# hub_keyboard.net
KiCad netlist of a schematic drawn in EAGLE
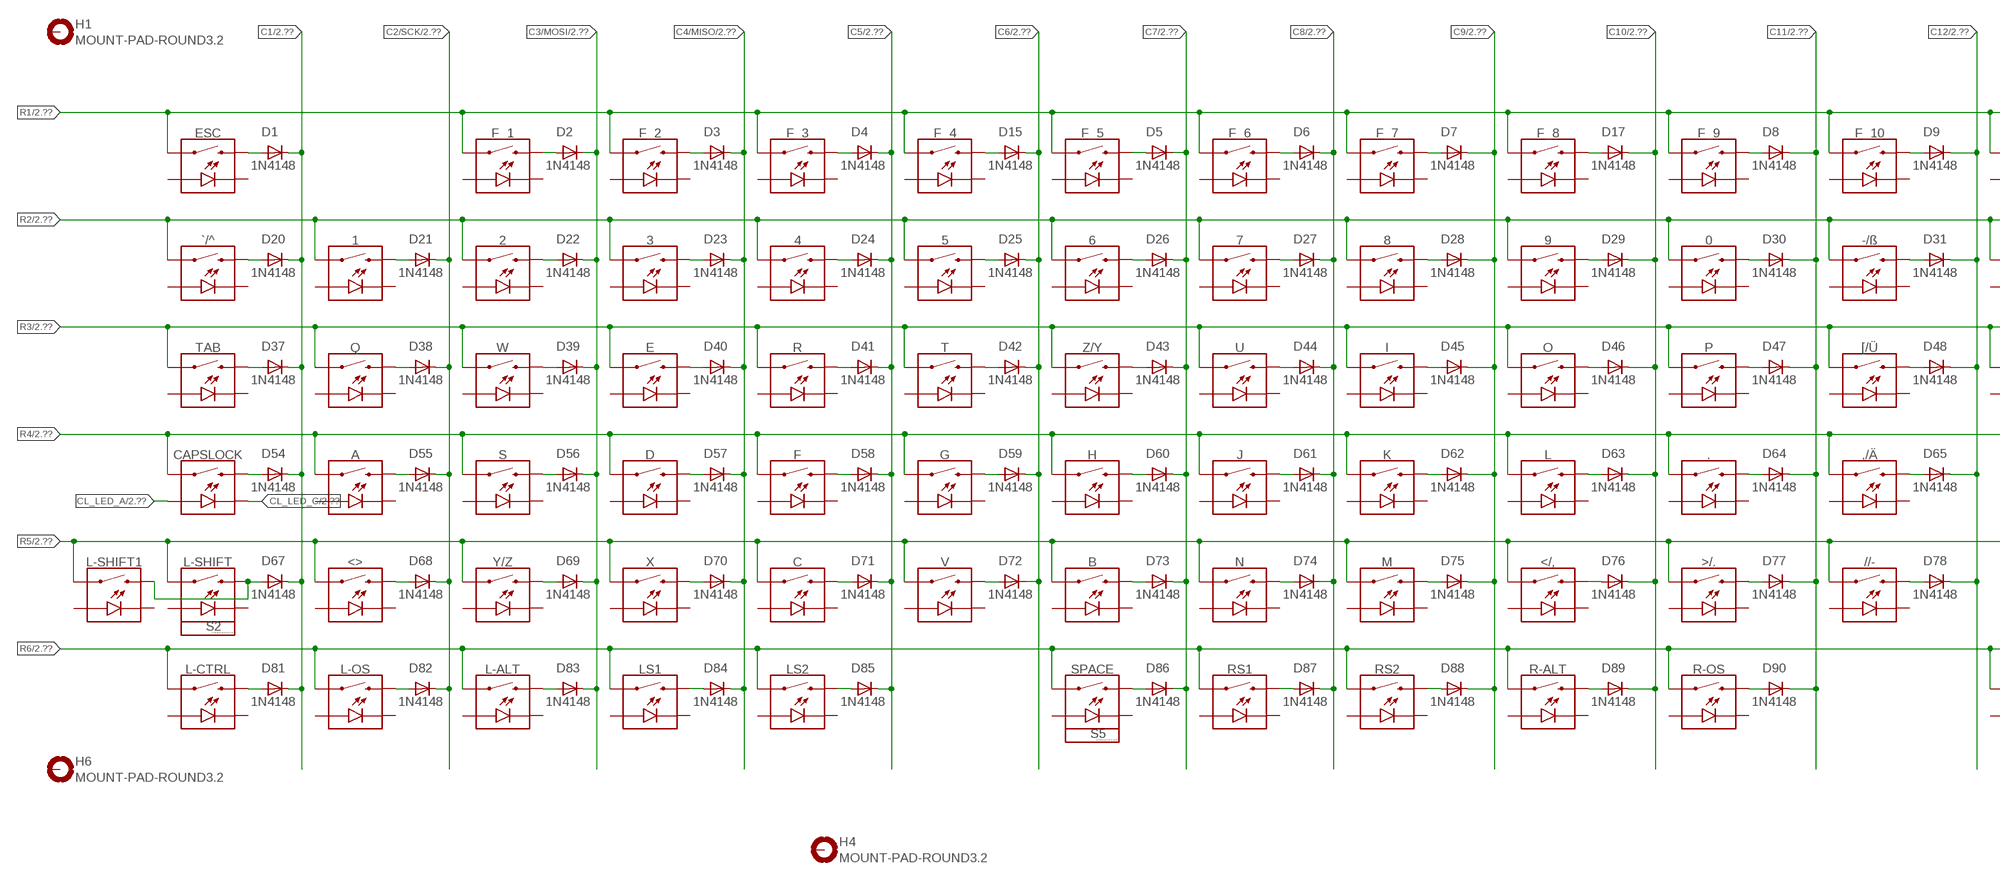
[diagram p0: schematic, sheet 1, part 1 of 2]
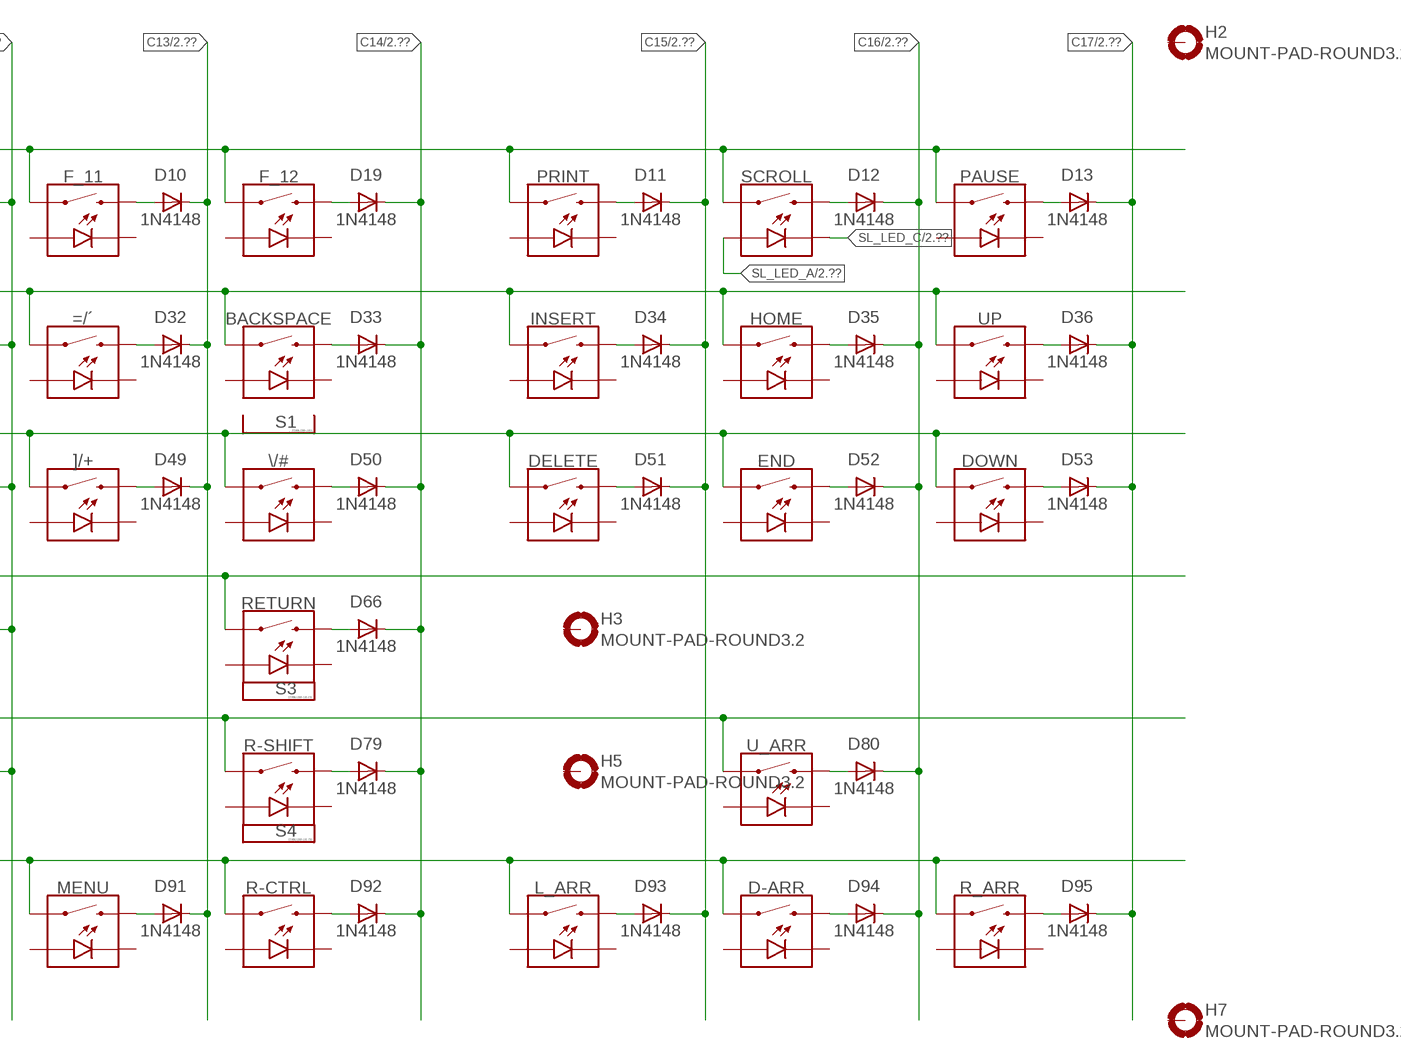
[diagram p1: schematic, sheet 1, part 2 of 2]
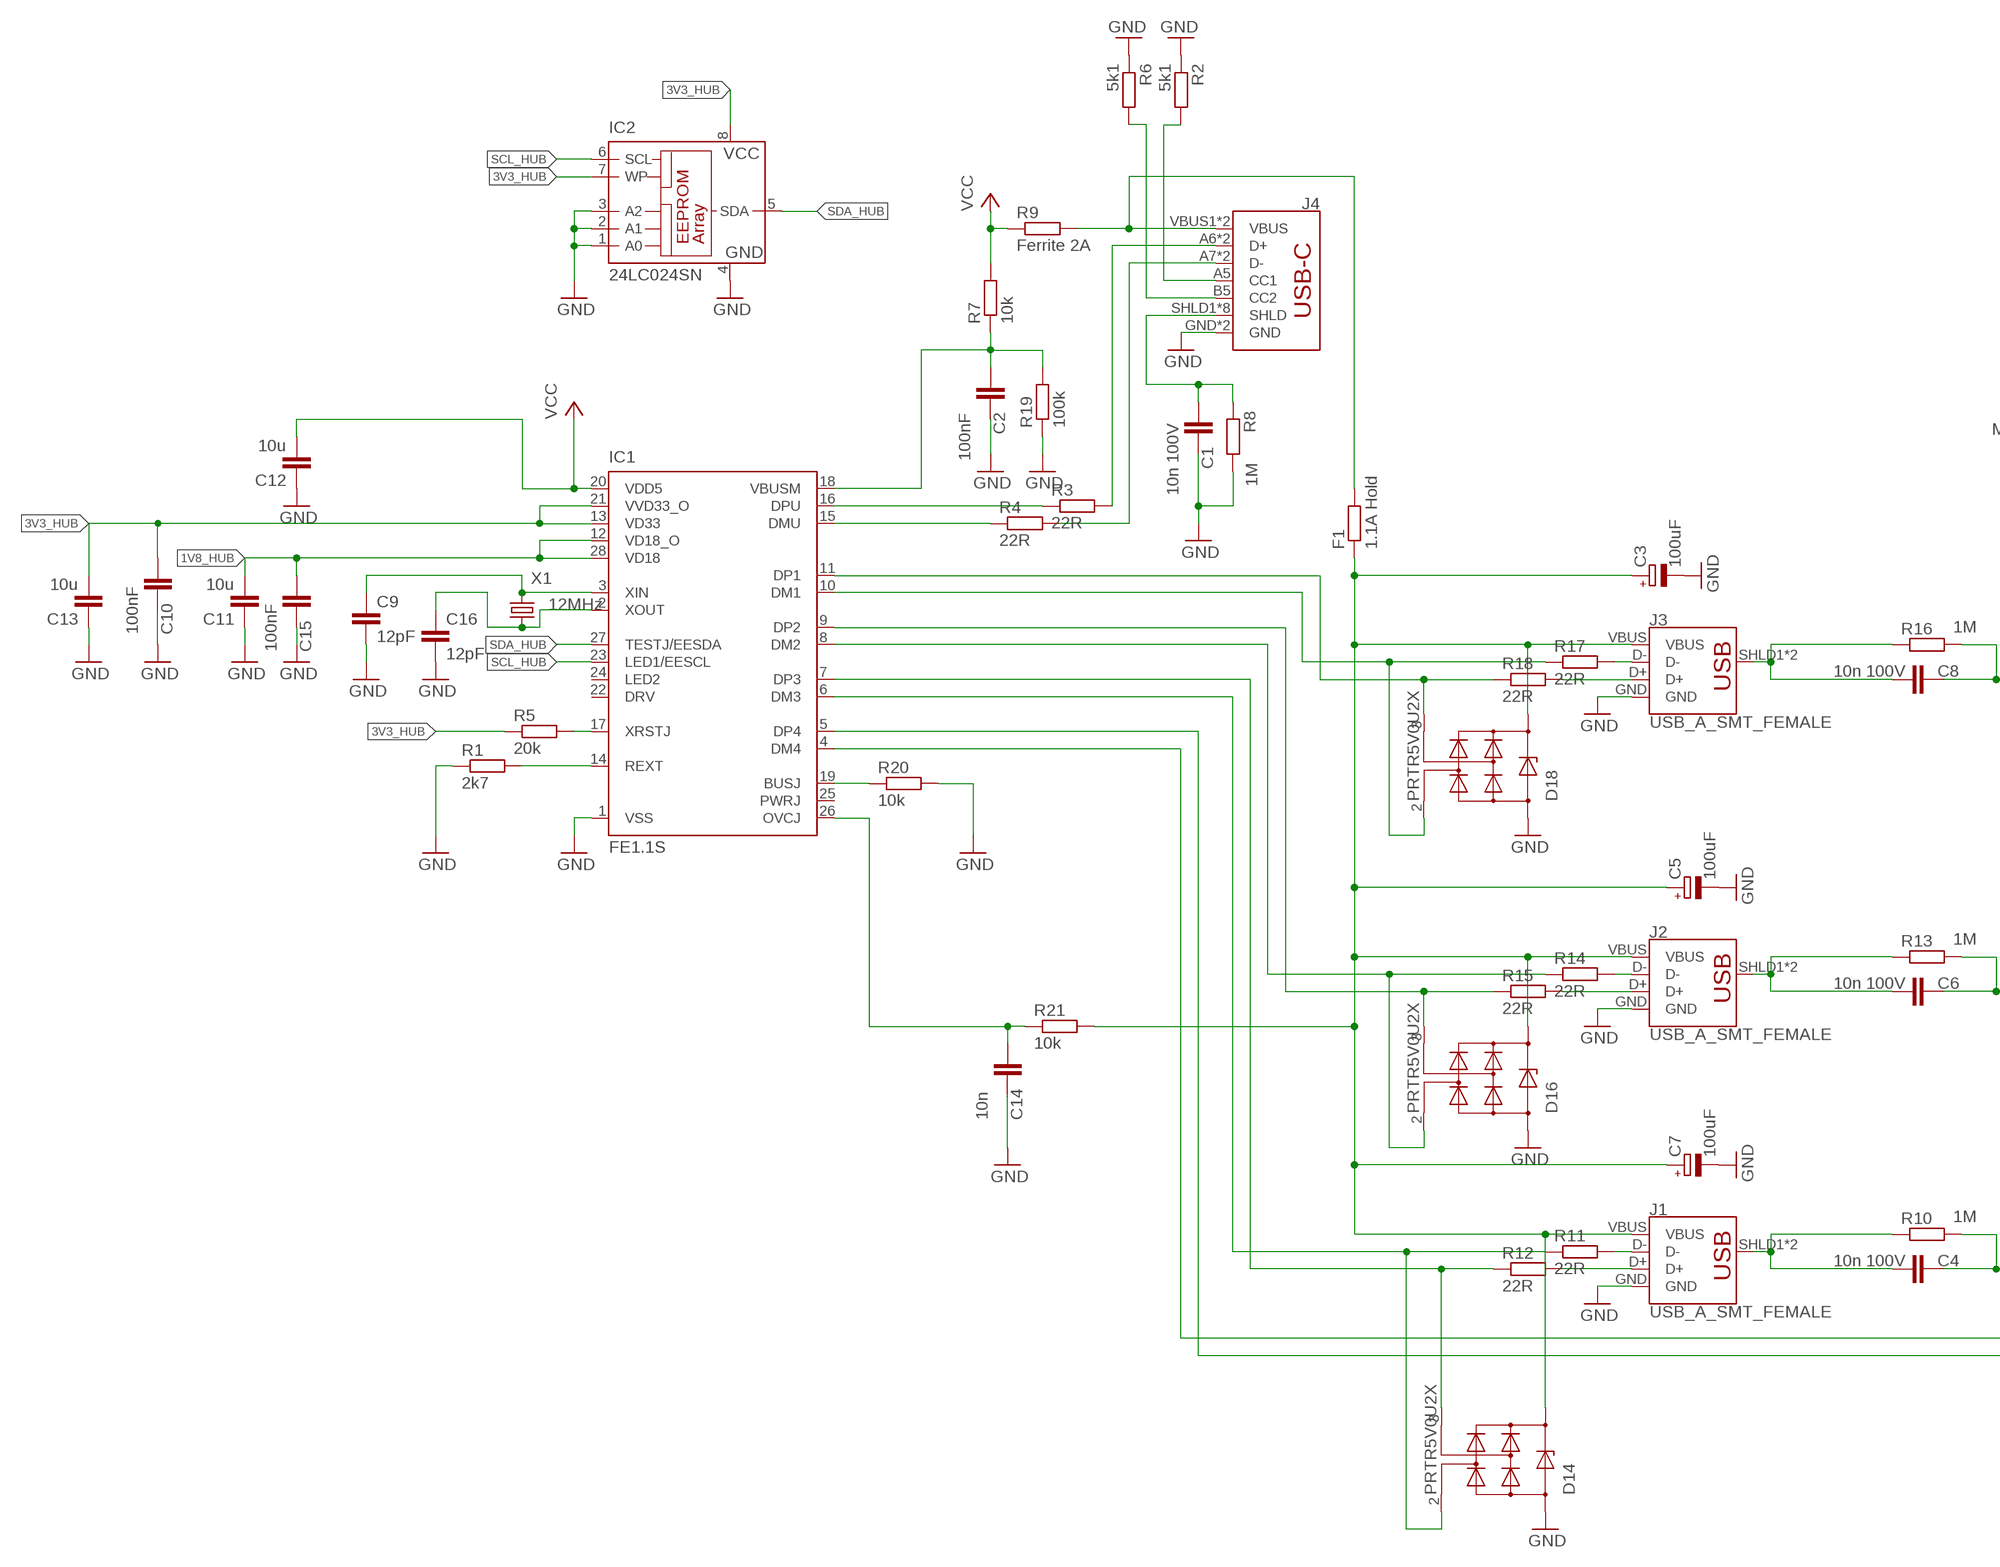
[diagram p2: schematic, sheet 2, part 1 of 2]
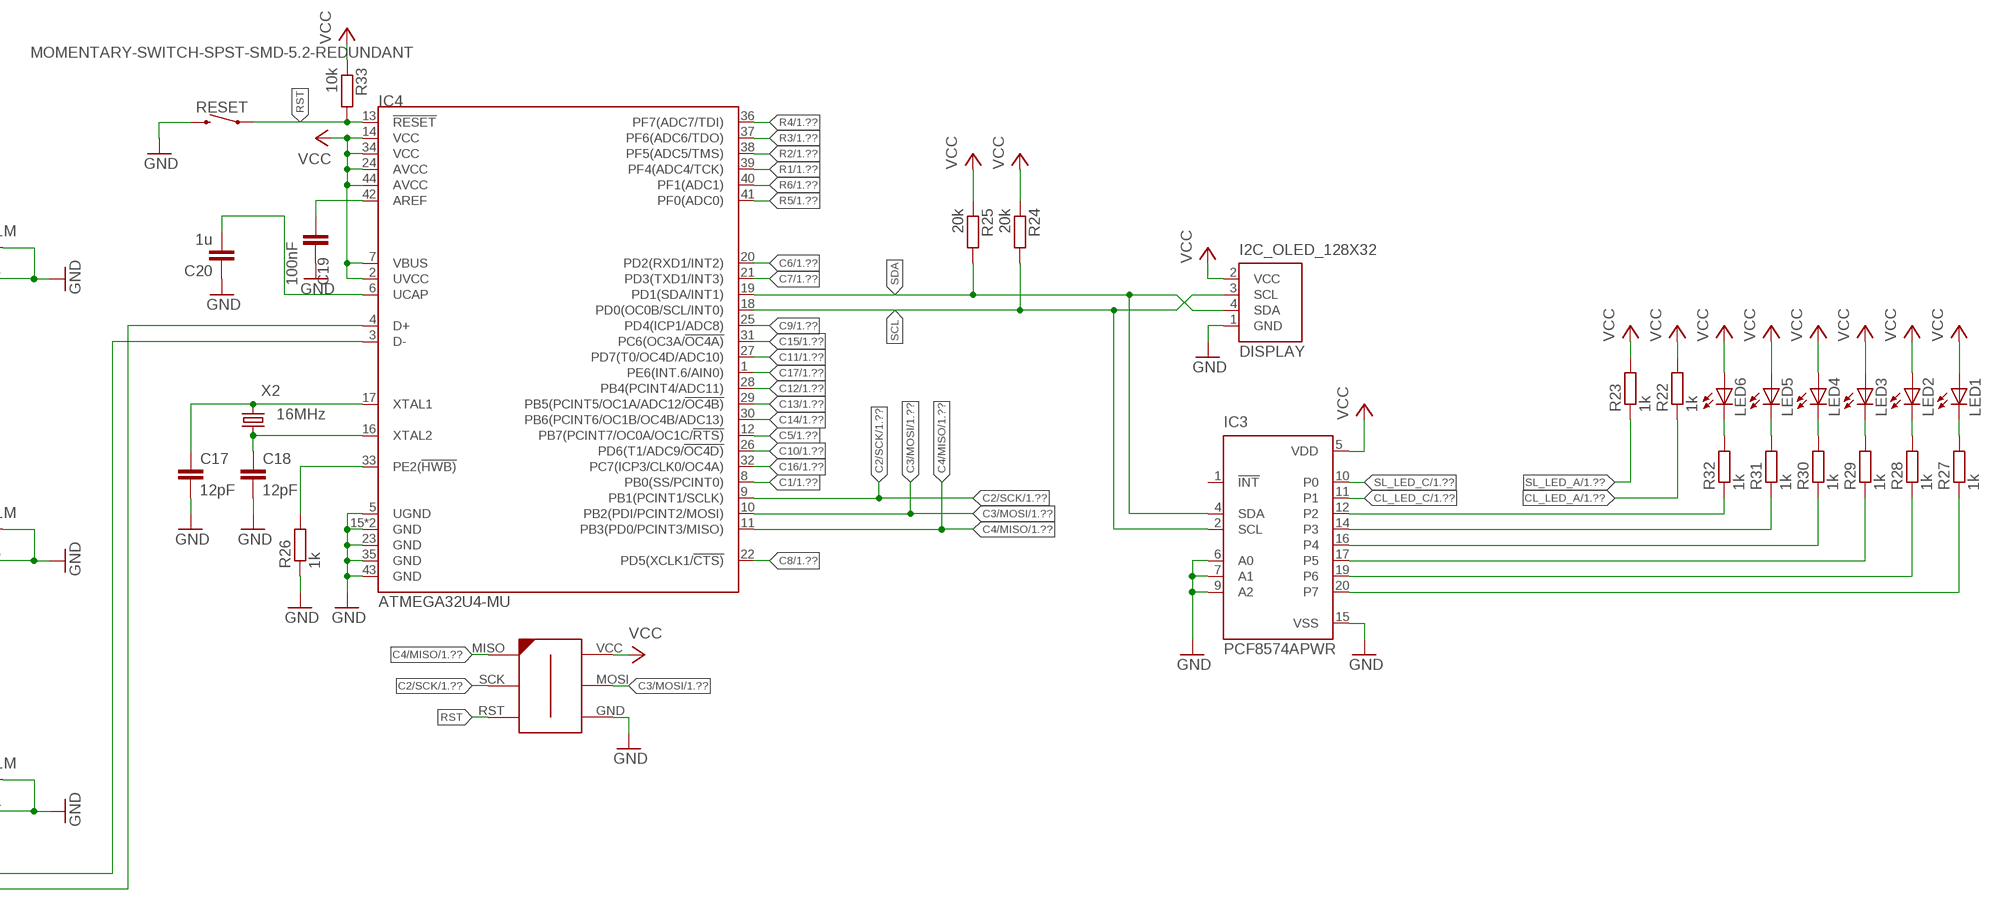
[diagram p3: schematic, sheet 2, part 2 of 2]

(export (version "E")
  (design (tool "Eeschema 10.0.6"))
  (components
    (comp (ref ",/Ä")
      (value "MECHANICAL-KEYBOARD1U")
      (footprint "eagle-import:CHERRY-MX-LED-1U")
      (libsource (lib "eagle-import") (part "MECHANICAL-KEYBOARD1U"))
    )
    (comp (ref "-/ß")
      (value "MECHANICAL-KEYBOARD1U")
      (footprint "eagle-import:CHERRY-MX-LED-1U")
      (libsource (lib "eagle-import") (part "MECHANICAL-KEYBOARD1U"))
    )
    (comp (ref ".")
      (value "MECHANICAL-KEYBOARD1U")
      (footprint "eagle-import:CHERRY-MX-LED-1U")
      (libsource (lib "eagle-import") (part "MECHANICAL-KEYBOARD1U"))
    )
    (comp (ref "//-")
      (value "MECHANICAL-KEYBOARD1U")
      (footprint "eagle-import:CHERRY-MX-LED-1U")
      (libsource (lib "eagle-import") (part "MECHANICAL-KEYBOARD1U"))
    )
    (comp (ref "0")
      (value "MECHANICAL-KEYBOARD1U")
      (footprint "eagle-import:CHERRY-MX-LED-1U")
      (libsource (lib "eagle-import") (part "MECHANICAL-KEYBOARD1U"))
    )
    (comp (ref "1")
      (value "MECHANICAL-KEYBOARD1U")
      (footprint "eagle-import:CHERRY-MX-LED-1U")
      (libsource (lib "eagle-import") (part "MECHANICAL-KEYBOARD1U"))
    )
    (comp (ref "2")
      (value "MECHANICAL-KEYBOARD1U")
      (footprint "eagle-import:CHERRY-MX-LED-1U")
      (libsource (lib "eagle-import") (part "MECHANICAL-KEYBOARD1U"))
    )
    (comp (ref "3")
      (value "MECHANICAL-KEYBOARD1U")
      (footprint "eagle-import:CHERRY-MX-LED-1U")
      (libsource (lib "eagle-import") (part "MECHANICAL-KEYBOARD1U"))
    )
    (comp (ref "4")
      (value "MECHANICAL-KEYBOARD1U")
      (footprint "eagle-import:CHERRY-MX-LED-1U")
      (libsource (lib "eagle-import") (part "MECHANICAL-KEYBOARD1U"))
    )
    (comp (ref "5")
      (value "MECHANICAL-KEYBOARD1U")
      (footprint "eagle-import:CHERRY-MX-LED-1U")
      (libsource (lib "eagle-import") (part "MECHANICAL-KEYBOARD1U"))
    )
    (comp (ref "6")
      (value "MECHANICAL-KEYBOARD1U")
      (footprint "eagle-import:CHERRY-MX-LED-1U")
      (libsource (lib "eagle-import") (part "MECHANICAL-KEYBOARD1U"))
    )
    (comp (ref "7")
      (value "MECHANICAL-KEYBOARD1U")
      (footprint "eagle-import:CHERRY-MX-LED-1U")
      (libsource (lib "eagle-import") (part "MECHANICAL-KEYBOARD1U"))
    )
    (comp (ref "8")
      (value "MECHANICAL-KEYBOARD1U")
      (footprint "eagle-import:CHERRY-MX-LED-1U")
      (libsource (lib "eagle-import") (part "MECHANICAL-KEYBOARD1U"))
    )
    (comp (ref "9")
      (value "MECHANICAL-KEYBOARD1U")
      (footprint "eagle-import:CHERRY-MX-LED-1U")
      (libsource (lib "eagle-import") (part "MECHANICAL-KEYBOARD1U"))
    )
    (comp (ref "</,")
      (value "MECHANICAL-KEYBOARD1U")
      (footprint "eagle-import:CHERRY-MX-LED-1U")
      (libsource (lib "eagle-import") (part "MECHANICAL-KEYBOARD1U"))
    )
    (comp (ref "<>")
      (value "MECHANICAL-KEYBOARD1U")
      (footprint "eagle-import:CHERRY-MX-LED-1U")
      (libsource (lib "eagle-import") (part "MECHANICAL-KEYBOARD1U"))
    )
    (comp (ref "=/´")
      (value "MECHANICAL-KEYBOARD1U")
      (footprint "eagle-import:CHERRY-MX-LED-1U")
      (libsource (lib "eagle-import") (part "MECHANICAL-KEYBOARD1U"))
    )
    (comp (ref ">/.")
      (value "MECHANICAL-KEYBOARD1U")
      (footprint "eagle-import:CHERRY-MX-LED-1U")
      (libsource (lib "eagle-import") (part "MECHANICAL-KEYBOARD1U"))
    )
    (comp (ref "A")
      (value "MECHANICAL-KEYBOARD1U")
      (footprint "eagle-import:CHERRY-MX-LED-1U")
      (libsource (lib "eagle-import") (part "MECHANICAL-KEYBOARD1U"))
    )
    (comp (ref "B")
      (value "MECHANICAL-KEYBOARD1U")
      (footprint "eagle-import:CHERRY-MX-LED-1U")
      (libsource (lib "eagle-import") (part "MECHANICAL-KEYBOARD1U"))
    )
    (comp (ref "BACKSPACE")
      (value "MECHANICAL-KEYBOARD2U")
      (footprint "eagle-import:CHERRY-MX-LED-1X2U")
      (libsource (lib "eagle-import") (part "MECHANICAL-KEYBOARD2U"))
    )
    (comp (ref "C")
      (value "MECHANICAL-KEYBOARD1U")
      (footprint "eagle-import:CHERRY-MX-LED-1U")
      (libsource (lib "eagle-import") (part "MECHANICAL-KEYBOARD1U"))
    )
    (comp (ref "CAPSLOCK")
      (value "MECHANICAL-KEYBOARD1.75U")
      (footprint "eagle-import:CHERRY-MX-LED-1.75U")
      (libsource (lib "eagle-import") (part "MECHANICAL-KEYBOARD1.75U"))
    )
    (comp (ref "D")
      (value "MECHANICAL-KEYBOARD1U")
      (footprint "eagle-import:CHERRY-MX-LED-1U")
      (libsource (lib "eagle-import") (part "MECHANICAL-KEYBOARD1U"))
    )
    (comp (ref "D-ARR")
      (value "MECHANICAL-KEYBOARD1U")
      (footprint "eagle-import:CHERRY-MX-LED-1U")
      (libsource (lib "eagle-import") (part "MECHANICAL-KEYBOARD1U"))
    )
    (comp (ref "D1")
      (value "1N4148")
      (footprint "eagle-import:SOD123")
      (libsource (lib "eagle-import") (part "DIODE-SOD123"))
    )
    (comp (ref "D2")
      (value "1N4148")
      (footprint "eagle-import:SOD123")
      (libsource (lib "eagle-import") (part "DIODE-SOD123"))
    )
    (comp (ref "D3")
      (value "1N4148")
      (footprint "eagle-import:SOD123")
      (libsource (lib "eagle-import") (part "DIODE-SOD123"))
    )
    (comp (ref "D4")
      (value "1N4148")
      (footprint "eagle-import:SOD123")
      (libsource (lib "eagle-import") (part "DIODE-SOD123"))
    )
    (comp (ref "D5")
      (value "1N4148")
      (footprint "eagle-import:SOD123")
      (libsource (lib "eagle-import") (part "DIODE-SOD123"))
    )
    (comp (ref "D6")
      (value "1N4148")
      (footprint "eagle-import:SOD123")
      (libsource (lib "eagle-import") (part "DIODE-SOD123"))
    )
    (comp (ref "D7")
      (value "1N4148")
      (footprint "eagle-import:SOD123")
      (libsource (lib "eagle-import") (part "DIODE-SOD123"))
    )
    (comp (ref "D8")
      (value "1N4148")
      (footprint "eagle-import:SOD123")
      (libsource (lib "eagle-import") (part "DIODE-SOD123"))
    )
    (comp (ref "D9")
      (value "1N4148")
      (footprint "eagle-import:SOD123")
      (libsource (lib "eagle-import") (part "DIODE-SOD123"))
    )
    (comp (ref "D10")
      (value "1N4148")
      (footprint "eagle-import:SOD123")
      (libsource (lib "eagle-import") (part "DIODE-SOD123"))
    )
    (comp (ref "D11")
      (value "1N4148")
      (footprint "eagle-import:SOD123")
      (libsource (lib "eagle-import") (part "DIODE-SOD123"))
    )
    (comp (ref "D12")
      (value "1N4148")
      (footprint "eagle-import:SOD123")
      (libsource (lib "eagle-import") (part "DIODE-SOD123"))
    )
    (comp (ref "D13")
      (value "1N4148")
      (footprint "eagle-import:SOD123")
      (libsource (lib "eagle-import") (part "DIODE-SOD123"))
    )
    (comp (ref "D15")
      (value "1N4148")
      (footprint "eagle-import:SOD123")
      (libsource (lib "eagle-import") (part "DIODE-SOD123"))
    )
    (comp (ref "D17")
      (value "1N4148")
      (footprint "eagle-import:SOD123")
      (libsource (lib "eagle-import") (part "DIODE-SOD123"))
    )
    (comp (ref "D19")
      (value "1N4148")
      (footprint "eagle-import:SOD123")
      (libsource (lib "eagle-import") (part "DIODE-SOD123"))
    )
    (comp (ref "D20")
      (value "1N4148")
      (footprint "eagle-import:SOD123")
      (libsource (lib "eagle-import") (part "DIODE-SOD123"))
    )
    (comp (ref "D21")
      (value "1N4148")
      (footprint "eagle-import:SOD123")
      (libsource (lib "eagle-import") (part "DIODE-SOD123"))
    )
    (comp (ref "D22")
      (value "1N4148")
      (footprint "eagle-import:SOD123")
      (libsource (lib "eagle-import") (part "DIODE-SOD123"))
    )
    (comp (ref "D23")
      (value "1N4148")
      (footprint "eagle-import:SOD123")
      (libsource (lib "eagle-import") (part "DIODE-SOD123"))
    )
    (comp (ref "D24")
      (value "1N4148")
      (footprint "eagle-import:SOD123")
      (libsource (lib "eagle-import") (part "DIODE-SOD123"))
    )
    (comp (ref "D25")
      (value "1N4148")
      (footprint "eagle-import:SOD123")
      (libsource (lib "eagle-import") (part "DIODE-SOD123"))
    )
    (comp (ref "D26")
      (value "1N4148")
      (footprint "eagle-import:SOD123")
      (libsource (lib "eagle-import") (part "DIODE-SOD123"))
    )
    (comp (ref "D27")
      (value "1N4148")
      (footprint "eagle-import:SOD123")
      (libsource (lib "eagle-import") (part "DIODE-SOD123"))
    )
    (comp (ref "D28")
      (value "1N4148")
      (footprint "eagle-import:SOD123")
      (libsource (lib "eagle-import") (part "DIODE-SOD123"))
    )
    (comp (ref "D29")
      (value "1N4148")
      (footprint "eagle-import:SOD123")
      (libsource (lib "eagle-import") (part "DIODE-SOD123"))
    )
    (comp (ref "D30")
      (value "1N4148")
      (footprint "eagle-import:SOD123")
      (libsource (lib "eagle-import") (part "DIODE-SOD123"))
    )
    (comp (ref "D31")
      (value "1N4148")
      (footprint "eagle-import:SOD123")
      (libsource (lib "eagle-import") (part "DIODE-SOD123"))
    )
    (comp (ref "D32")
      (value "1N4148")
      (footprint "eagle-import:SOD123")
      (libsource (lib "eagle-import") (part "DIODE-SOD123"))
    )
    (comp (ref "D33")
      (value "1N4148")
      (footprint "eagle-import:SOD123")
      (libsource (lib "eagle-import") (part "DIODE-SOD123"))
    )
    (comp (ref "D34")
      (value "1N4148")
      (footprint "eagle-import:SOD123")
      (libsource (lib "eagle-import") (part "DIODE-SOD123"))
    )
    (comp (ref "D35")
      (value "1N4148")
      (footprint "eagle-import:SOD123")
      (libsource (lib "eagle-import") (part "DIODE-SOD123"))
    )
    (comp (ref "D36")
      (value "1N4148")
      (footprint "eagle-import:SOD123")
      (libsource (lib "eagle-import") (part "DIODE-SOD123"))
    )
    (comp (ref "D37")
      (value "1N4148")
      (footprint "eagle-import:SOD123")
      (libsource (lib "eagle-import") (part "DIODE-SOD123"))
    )
    (comp (ref "D38")
      (value "1N4148")
      (footprint "eagle-import:SOD123")
      (libsource (lib "eagle-import") (part "DIODE-SOD123"))
    )
    (comp (ref "D39")
      (value "1N4148")
      (footprint "eagle-import:SOD123")
      (libsource (lib "eagle-import") (part "DIODE-SOD123"))
    )
    (comp (ref "D40")
      (value "1N4148")
      (footprint "eagle-import:SOD123")
      (libsource (lib "eagle-import") (part "DIODE-SOD123"))
    )
    (comp (ref "D41")
      (value "1N4148")
      (footprint "eagle-import:SOD123")
      (libsource (lib "eagle-import") (part "DIODE-SOD123"))
    )
    (comp (ref "D42")
      (value "1N4148")
      (footprint "eagle-import:SOD123")
      (libsource (lib "eagle-import") (part "DIODE-SOD123"))
    )
    (comp (ref "D43")
      (value "1N4148")
      (footprint "eagle-import:SOD123")
      (libsource (lib "eagle-import") (part "DIODE-SOD123"))
    )
    (comp (ref "D44")
      (value "1N4148")
      (footprint "eagle-import:SOD123")
      (libsource (lib "eagle-import") (part "DIODE-SOD123"))
    )
    (comp (ref "D45")
      (value "1N4148")
      (footprint "eagle-import:SOD123")
      (libsource (lib "eagle-import") (part "DIODE-SOD123"))
    )
    (comp (ref "D46")
      (value "1N4148")
      (footprint "eagle-import:SOD123")
      (libsource (lib "eagle-import") (part "DIODE-SOD123"))
    )
    (comp (ref "D47")
      (value "1N4148")
      (footprint "eagle-import:SOD123")
      (libsource (lib "eagle-import") (part "DIODE-SOD123"))
    )
    (comp (ref "D48")
      (value "1N4148")
      (footprint "eagle-import:SOD123")
      (libsource (lib "eagle-import") (part "DIODE-SOD123"))
    )
    (comp (ref "D49")
      (value "1N4148")
      (footprint "eagle-import:SOD123")
      (libsource (lib "eagle-import") (part "DIODE-SOD123"))
    )
    (comp (ref "D50")
      (value "1N4148")
      (footprint "eagle-import:SOD123")
      (libsource (lib "eagle-import") (part "DIODE-SOD123"))
    )
    (comp (ref "D51")
      (value "1N4148")
      (footprint "eagle-import:SOD123")
      (libsource (lib "eagle-import") (part "DIODE-SOD123"))
    )
    (comp (ref "D52")
      (value "1N4148")
      (footprint "eagle-import:SOD123")
      (libsource (lib "eagle-import") (part "DIODE-SOD123"))
    )
    (comp (ref "D53")
      (value "1N4148")
      (footprint "eagle-import:SOD123")
      (libsource (lib "eagle-import") (part "DIODE-SOD123"))
    )
    (comp (ref "D54")
      (value "1N4148")
      (footprint "eagle-import:SOD123")
      (libsource (lib "eagle-import") (part "DIODE-SOD123"))
    )
    (comp (ref "D55")
      (value "1N4148")
      (footprint "eagle-import:SOD123")
      (libsource (lib "eagle-import") (part "DIODE-SOD123"))
    )
    (comp (ref "D56")
      (value "1N4148")
      (footprint "eagle-import:SOD123")
      (libsource (lib "eagle-import") (part "DIODE-SOD123"))
    )
    (comp (ref "D57")
      (value "1N4148")
      (footprint "eagle-import:SOD123")
      (libsource (lib "eagle-import") (part "DIODE-SOD123"))
    )
    (comp (ref "D58")
      (value "1N4148")
      (footprint "eagle-import:SOD123")
      (libsource (lib "eagle-import") (part "DIODE-SOD123"))
    )
    (comp (ref "D59")
      (value "1N4148")
      (footprint "eagle-import:SOD123")
      (libsource (lib "eagle-import") (part "DIODE-SOD123"))
    )
    (comp (ref "D60")
      (value "1N4148")
      (footprint "eagle-import:SOD123")
      (libsource (lib "eagle-import") (part "DIODE-SOD123"))
    )
    (comp (ref "D61")
      (value "1N4148")
      (footprint "eagle-import:SOD123")
      (libsource (lib "eagle-import") (part "DIODE-SOD123"))
    )
    (comp (ref "D62")
      (value "1N4148")
      (footprint "eagle-import:SOD123")
      (libsource (lib "eagle-import") (part "DIODE-SOD123"))
    )
    (comp (ref "D63")
      (value "1N4148")
      (footprint "eagle-import:SOD123")
      (libsource (lib "eagle-import") (part "DIODE-SOD123"))
    )
    (comp (ref "D64")
      (value "1N4148")
      (footprint "eagle-import:SOD123")
      (libsource (lib "eagle-import") (part "DIODE-SOD123"))
    )
    (comp (ref "D65")
      (value "1N4148")
      (footprint "eagle-import:SOD123")
      (libsource (lib "eagle-import") (part "DIODE-SOD123"))
    )
    (comp (ref "D66")
      (value "1N4148")
      (footprint "eagle-import:SOD123")
      (libsource (lib "eagle-import") (part "DIODE-SOD123"))
    )
    (comp (ref "D67")
      (value "1N4148")
      (footprint "eagle-import:SOD123")
      (libsource (lib "eagle-import") (part "DIODE-SOD123"))
    )
    (comp (ref "D68")
      (value "1N4148")
      (footprint "eagle-import:SOD123")
      (libsource (lib "eagle-import") (part "DIODE-SOD123"))
    )
    (comp (ref "D69")
      (value "1N4148")
      (footprint "eagle-import:SOD123")
      (libsource (lib "eagle-import") (part "DIODE-SOD123"))
    )
    (comp (ref "D70")
      (value "1N4148")
      (footprint "eagle-import:SOD123")
      (libsource (lib "eagle-import") (part "DIODE-SOD123"))
    )
    (comp (ref "D71")
      (value "1N4148")
      (footprint "eagle-import:SOD123")
      (libsource (lib "eagle-import") (part "DIODE-SOD123"))
    )
    (comp (ref "D72")
      (value "1N4148")
      (footprint "eagle-import:SOD123")
      (libsource (lib "eagle-import") (part "DIODE-SOD123"))
    )
    (comp (ref "D73")
      (value "1N4148")
      (footprint "eagle-import:SOD123")
      (libsource (lib "eagle-import") (part "DIODE-SOD123"))
    )
    (comp (ref "D74")
      (value "1N4148")
      (footprint "eagle-import:SOD123")
      (libsource (lib "eagle-import") (part "DIODE-SOD123"))
    )
    (comp (ref "D75")
      (value "1N4148")
      (footprint "eagle-import:SOD123")
      (libsource (lib "eagle-import") (part "DIODE-SOD123"))
    )
    (comp (ref "D76")
      (value "1N4148")
      (footprint "eagle-import:SOD123")
      (libsource (lib "eagle-import") (part "DIODE-SOD123"))
    )
    (comp (ref "D77")
      (value "1N4148")
      (footprint "eagle-import:SOD123")
      (libsource (lib "eagle-import") (part "DIODE-SOD123"))
    )
    (comp (ref "D78")
      (value "1N4148")
      (footprint "eagle-import:SOD123")
      (libsource (lib "eagle-import") (part "DIODE-SOD123"))
    )
    (comp (ref "D79")
      (value "1N4148")
      (footprint "eagle-import:SOD123")
      (libsource (lib "eagle-import") (part "DIODE-SOD123"))
    )
    (comp (ref "D80")
      (value "1N4148")
      (footprint "eagle-import:SOD123")
      (libsource (lib "eagle-import") (part "DIODE-SOD123"))
    )
    (comp (ref "D81")
      (value "1N4148")
      (footprint "eagle-import:SOD123")
      (libsource (lib "eagle-import") (part "DIODE-SOD123"))
    )
    (comp (ref "D82")
      (value "1N4148")
      (footprint "eagle-import:SOD123")
      (libsource (lib "eagle-import") (part "DIODE-SOD123"))
    )
    (comp (ref "D83")
      (value "1N4148")
      (footprint "eagle-import:SOD123")
      (libsource (lib "eagle-import") (part "DIODE-SOD123"))
    )
    (comp (ref "D84")
      (value "1N4148")
      (footprint "eagle-import:SOD123")
      (libsource (lib "eagle-import") (part "DIODE-SOD123"))
    )
    (comp (ref "D85")
      (value "1N4148")
      (footprint "eagle-import:SOD123")
      (libsource (lib "eagle-import") (part "DIODE-SOD123"))
    )
    (comp (ref "D86")
      (value "1N4148")
      (footprint "eagle-import:SOD123")
      (libsource (lib "eagle-import") (part "DIODE-SOD123"))
    )
    (comp (ref "D87")
      (value "1N4148")
      (footprint "eagle-import:SOD123")
      (libsource (lib "eagle-import") (part "DIODE-SOD123"))
    )
    (comp (ref "D88")
      (value "1N4148")
      (footprint "eagle-import:SOD123")
      (libsource (lib "eagle-import") (part "DIODE-SOD123"))
    )
    (comp (ref "D89")
      (value "1N4148")
      (footprint "eagle-import:SOD123")
      (libsource (lib "eagle-import") (part "DIODE-SOD123"))
    )
    (comp (ref "D90")
      (value "1N4148")
      (footprint "eagle-import:SOD123")
      (libsource (lib "eagle-import") (part "DIODE-SOD123"))
    )
    (comp (ref "D91")
      (value "1N4148")
      (footprint "eagle-import:SOD123")
      (libsource (lib "eagle-import") (part "DIODE-SOD123"))
    )
    (comp (ref "D92")
      (value "1N4148")
      (footprint "eagle-import:SOD123")
      (libsource (lib "eagle-import") (part "DIODE-SOD123"))
    )
    (comp (ref "D93")
      (value "1N4148")
      (footprint "eagle-import:SOD123")
      (libsource (lib "eagle-import") (part "DIODE-SOD123"))
    )
    (comp (ref "D94")
      (value "1N4148")
      (footprint "eagle-import:SOD123")
      (libsource (lib "eagle-import") (part "DIODE-SOD123"))
    )
    (comp (ref "D95")
      (value "1N4148")
      (footprint "eagle-import:SOD123")
      (libsource (lib "eagle-import") (part "DIODE-SOD123"))
    )
    (comp (ref "DELETE")
      (value "MECHANICAL-KEYBOARD1U")
      (footprint "eagle-import:CHERRY-MX-LED-1U")
      (libsource (lib "eagle-import") (part "MECHANICAL-KEYBOARD1U"))
    )
    (comp (ref "DOWN")
      (value "MECHANICAL-KEYBOARD1U")
      (footprint "eagle-import:CHERRY-MX-LED-1U")
      (libsource (lib "eagle-import") (part "MECHANICAL-KEYBOARD1U"))
    )
    (comp (ref "E")
      (value "MECHANICAL-KEYBOARD1U")
      (footprint "eagle-import:CHERRY-MX-LED-1U")
      (libsource (lib "eagle-import") (part "MECHANICAL-KEYBOARD1U"))
    )
    (comp (ref "END")
      (value "MECHANICAL-KEYBOARD1U")
      (footprint "eagle-import:CHERRY-MX-LED-1U")
      (libsource (lib "eagle-import") (part "MECHANICAL-KEYBOARD1U"))
    )
    (comp (ref "ESC")
      (value "MECHANICAL-KEYBOARD1U")
      (footprint "eagle-import:CHERRY-MX-LED-1U")
      (libsource (lib "eagle-import") (part "MECHANICAL-KEYBOARD1U"))
    )
    (comp (ref "F")
      (value "MECHANICAL-KEYBOARD1U")
      (footprint "eagle-import:CHERRY-MX-LED-1U")
      (libsource (lib "eagle-import") (part "MECHANICAL-KEYBOARD1U"))
    )
    (comp (ref "F_1")
      (value "MECHANICAL-KEYBOARD1U")
      (footprint "eagle-import:CHERRY-MX-LED-1U")
      (libsource (lib "eagle-import") (part "MECHANICAL-KEYBOARD1U"))
    )
    (comp (ref "F_2")
      (value "MECHANICAL-KEYBOARD1U")
      (footprint "eagle-import:CHERRY-MX-LED-1U")
      (libsource (lib "eagle-import") (part "MECHANICAL-KEYBOARD1U"))
    )
    (comp (ref "F_3")
      (value "MECHANICAL-KEYBOARD1U")
      (footprint "eagle-import:CHERRY-MX-LED-1U")
      (libsource (lib "eagle-import") (part "MECHANICAL-KEYBOARD1U"))
    )
    (comp (ref "F_4")
      (value "MECHANICAL-KEYBOARD1U")
      (footprint "eagle-import:CHERRY-MX-LED-1U")
      (libsource (lib "eagle-import") (part "MECHANICAL-KEYBOARD1U"))
    )
    (comp (ref "F_5")
      (value "MECHANICAL-KEYBOARD1U")
      (footprint "eagle-import:CHERRY-MX-LED-1U")
      (libsource (lib "eagle-import") (part "MECHANICAL-KEYBOARD1U"))
    )
    (comp (ref "F_6")
      (value "MECHANICAL-KEYBOARD1U")
      (footprint "eagle-import:CHERRY-MX-LED-1U")
      (libsource (lib "eagle-import") (part "MECHANICAL-KEYBOARD1U"))
    )
    (comp (ref "F_7")
      (value "MECHANICAL-KEYBOARD1U")
      (footprint "eagle-import:CHERRY-MX-LED-1U")
      (libsource (lib "eagle-import") (part "MECHANICAL-KEYBOARD1U"))
    )
    (comp (ref "F_8")
      (value "MECHANICAL-KEYBOARD1U")
      (footprint "eagle-import:CHERRY-MX-LED-1U")
      (libsource (lib "eagle-import") (part "MECHANICAL-KEYBOARD1U"))
    )
    (comp (ref "F_9")
      (value "MECHANICAL-KEYBOARD1U")
      (footprint "eagle-import:CHERRY-MX-LED-1U")
      (libsource (lib "eagle-import") (part "MECHANICAL-KEYBOARD1U"))
    )
    (comp (ref "F_10")
      (value "MECHANICAL-KEYBOARD1U")
      (footprint "eagle-import:CHERRY-MX-LED-1U")
      (libsource (lib "eagle-import") (part "MECHANICAL-KEYBOARD1U"))
    )
    (comp (ref "F_11")
      (value "MECHANICAL-KEYBOARD1U")
      (footprint "eagle-import:CHERRY-MX-LED-1U")
      (libsource (lib "eagle-import") (part "MECHANICAL-KEYBOARD1U"))
    )
    (comp (ref "F_12")
      (value "MECHANICAL-KEYBOARD1U")
      (footprint "eagle-import:CHERRY-MX-LED-1U")
      (libsource (lib "eagle-import") (part "MECHANICAL-KEYBOARD1U"))
    )
    (comp (ref "G")
      (value "MECHANICAL-KEYBOARD1U")
      (footprint "eagle-import:CHERRY-MX-LED-1U")
      (libsource (lib "eagle-import") (part "MECHANICAL-KEYBOARD1U"))
    )
    (comp (ref "H")
      (value "MECHANICAL-KEYBOARD1U")
      (footprint "eagle-import:CHERRY-MX-LED-1U")
      (libsource (lib "eagle-import") (part "MECHANICAL-KEYBOARD1U"))
    )
    (comp (ref "H1")
      (value "MOUNT-PAD-ROUND3.2")
      (footprint "eagle-import:3,2-PAD")
      (libsource (lib "eagle-import") (part "MOUNT-PAD-ROUND3.2"))
    )
    (comp (ref "H2")
      (value "MOUNT-PAD-ROUND3.2")
      (footprint "eagle-import:3,2-PAD")
      (libsource (lib "eagle-import") (part "MOUNT-PAD-ROUND3.2"))
    )
    (comp (ref "H3")
      (value "MOUNT-PAD-ROUND3.2")
      (footprint "eagle-import:3,2-PAD")
      (libsource (lib "eagle-import") (part "MOUNT-PAD-ROUND3.2"))
    )
    (comp (ref "H4")
      (value "MOUNT-PAD-ROUND3.2")
      (footprint "eagle-import:3,2-PAD")
      (libsource (lib "eagle-import") (part "MOUNT-PAD-ROUND3.2"))
    )
    (comp (ref "H5")
      (value "MOUNT-PAD-ROUND3.2")
      (footprint "eagle-import:3,2-PAD")
      (libsource (lib "eagle-import") (part "MOUNT-PAD-ROUND3.2"))
    )
    (comp (ref "H6")
      (value "MOUNT-PAD-ROUND3.2")
      (footprint "eagle-import:3,2-PAD")
      (libsource (lib "eagle-import") (part "MOUNT-PAD-ROUND3.2"))
    )
    (comp (ref "H7")
      (value "MOUNT-PAD-ROUND3.2")
      (footprint "eagle-import:3,2-PAD")
      (libsource (lib "eagle-import") (part "MOUNT-PAD-ROUND3.2"))
    )
    (comp (ref "HOME")
      (value "MECHANICAL-KEYBOARD1U")
      (footprint "eagle-import:CHERRY-MX-LED-1U")
      (libsource (lib "eagle-import") (part "MECHANICAL-KEYBOARD1U"))
    )
    (comp (ref "I")
      (value "MECHANICAL-KEYBOARD1U")
      (footprint "eagle-import:CHERRY-MX-LED-1U")
      (libsource (lib "eagle-import") (part "MECHANICAL-KEYBOARD1U"))
    )
    (comp (ref "INSERT")
      (value "MECHANICAL-KEYBOARD1U")
      (footprint "eagle-import:CHERRY-MX-LED-1U")
      (libsource (lib "eagle-import") (part "MECHANICAL-KEYBOARD1U"))
    )
    (comp (ref "J")
      (value "MECHANICAL-KEYBOARD1U")
      (footprint "eagle-import:CHERRY-MX-LED-1U")
      (libsource (lib "eagle-import") (part "MECHANICAL-KEYBOARD1U"))
    )
    (comp (ref "K")
      (value "MECHANICAL-KEYBOARD1U")
      (footprint "eagle-import:CHERRY-MX-LED-1U")
      (libsource (lib "eagle-import") (part "MECHANICAL-KEYBOARD1U"))
    )
    (comp (ref "L")
      (value "MECHANICAL-KEYBOARD1U")
      (footprint "eagle-import:CHERRY-MX-LED-1U")
      (libsource (lib "eagle-import") (part "MECHANICAL-KEYBOARD1U"))
    )
    (comp (ref "L-ALT")
      (value "MECHANICAL-KEYBOARD1.25U")
      (footprint "eagle-import:CHERRY-MX-LED-1.25U")
      (libsource (lib "eagle-import") (part "MECHANICAL-KEYBOARD1.25U"))
    )
    (comp (ref "L-CTRL")
      (value "MECHANICAL-KEYBOARD1.25U")
      (footprint "eagle-import:CHERRY-MX-LED-1.25U")
      (libsource (lib "eagle-import") (part "MECHANICAL-KEYBOARD1.25U"))
    )
    (comp (ref "L-OS")
      (value "MECHANICAL-KEYBOARD1.25U")
      (footprint "eagle-import:CHERRY-MX-LED-1.25U")
      (libsource (lib "eagle-import") (part "MECHANICAL-KEYBOARD1.25U"))
    )
    (comp (ref "L-SHIFT")
      (value "MECHANICAL-KEYBOARD2.25U")
      (footprint "eagle-import:CHERRY-MX-LED-1X2.25")
      (libsource (lib "eagle-import") (part "MECHANICAL-KEYBOARD2.25U"))
    )
    (comp (ref "L-SHIFT1")
      (value "MECHANICAL-KEYBOARD1.25U")
      (footprint "eagle-import:CHERRY-MX-LED-1.25U")
      (libsource (lib "eagle-import") (part "MECHANICAL-KEYBOARD1.25U"))
    )
    (comp (ref "LS1")
      (value "MECHANICAL-KEYBOARD1.25U")
      (footprint "eagle-import:CHERRY-MX-LED-1.25U")
      (libsource (lib "eagle-import") (part "MECHANICAL-KEYBOARD1.25U"))
    )
    (comp (ref "LS2")
      (value "MECHANICAL-KEYBOARD1.25U")
      (footprint "eagle-import:CHERRY-MX-LED-1.25U")
      (libsource (lib "eagle-import") (part "MECHANICAL-KEYBOARD1.25U"))
    )
    (comp (ref "L_ARR")
      (value "MECHANICAL-KEYBOARD1U")
      (footprint "eagle-import:CHERRY-MX-LED-1U")
      (libsource (lib "eagle-import") (part "MECHANICAL-KEYBOARD1U"))
    )
    (comp (ref "M")
      (value "MECHANICAL-KEYBOARD1U")
      (footprint "eagle-import:CHERRY-MX-LED-1U")
      (libsource (lib "eagle-import") (part "MECHANICAL-KEYBOARD1U"))
    )
    (comp (ref "MENU")
      (value "MECHANICAL-KEYBOARD1.25U")
      (footprint "eagle-import:CHERRY-MX-LED-1.25U")
      (libsource (lib "eagle-import") (part "MECHANICAL-KEYBOARD1.25U"))
    )
    (comp (ref "N")
      (value "MECHANICAL-KEYBOARD1U")
      (footprint "eagle-import:CHERRY-MX-LED-1U")
      (libsource (lib "eagle-import") (part "MECHANICAL-KEYBOARD1U"))
    )
    (comp (ref "O")
      (value "MECHANICAL-KEYBOARD1U")
      (footprint "eagle-import:CHERRY-MX-LED-1U")
      (libsource (lib "eagle-import") (part "MECHANICAL-KEYBOARD1U"))
    )
    (comp (ref "P")
      (value "MECHANICAL-KEYBOARD1U")
      (footprint "eagle-import:CHERRY-MX-LED-1U")
      (libsource (lib "eagle-import") (part "MECHANICAL-KEYBOARD1U"))
    )
    (comp (ref "PAUSE")
      (value "MECHANICAL-KEYBOARD1U")
      (footprint "eagle-import:CHERRY-MX-LED-1U")
      (libsource (lib "eagle-import") (part "MECHANICAL-KEYBOARD1U"))
    )
    (comp (ref "PRINT")
      (value "MECHANICAL-KEYBOARD1U")
      (footprint "eagle-import:CHERRY-MX-LED-1U")
      (libsource (lib "eagle-import") (part "MECHANICAL-KEYBOARD1U"))
    )
    (comp (ref "Q")
      (value "MECHANICAL-KEYBOARD1U")
      (footprint "eagle-import:CHERRY-MX-LED-1U")
      (libsource (lib "eagle-import") (part "MECHANICAL-KEYBOARD1U"))
    )
    (comp (ref "R")
      (value "MECHANICAL-KEYBOARD1U")
      (footprint "eagle-import:CHERRY-MX-LED-1U")
      (libsource (lib "eagle-import") (part "MECHANICAL-KEYBOARD1U"))
    )
    (comp (ref "R-ALT")
      (value "MECHANICAL-KEYBOARD1.25U")
      (footprint "eagle-import:CHERRY-MX-LED-1.25U")
      (libsource (lib "eagle-import") (part "MECHANICAL-KEYBOARD1.25U"))
    )
    (comp (ref "R-CTRL")
      (value "MECHANICAL-KEYBOARD1.25U")
      (footprint "eagle-import:CHERRY-MX-LED-1.25U")
      (libsource (lib "eagle-import") (part "MECHANICAL-KEYBOARD1.25U"))
    )
    (comp (ref "R-OS")
      (value "MECHANICAL-KEYBOARD1.25U")
      (footprint "eagle-import:CHERRY-MX-LED-1.25U")
      (libsource (lib "eagle-import") (part "MECHANICAL-KEYBOARD1.25U"))
    )
    (comp (ref "R-SHIFT")
      (value "MECHANICAL-KEYBOARD2.75U")
      (footprint "eagle-import:CHERRY-MX-LED-1X2.75")
      (libsource (lib "eagle-import") (part "MECHANICAL-KEYBOARD2.75U"))
    )
    (comp (ref "RETURN")
      (value "MECHANICAL-KEYBOARD2.25U")
      (footprint "eagle-import:CHERRY-MX-LED-1X2.25")
      (libsource (lib "eagle-import") (part "MECHANICAL-KEYBOARD2.25U"))
    )
    (comp (ref "RS1")
      (value "MECHANICAL-KEYBOARD1.25U")
      (footprint "eagle-import:CHERRY-MX-LED-1.25U")
      (libsource (lib "eagle-import") (part "MECHANICAL-KEYBOARD1.25U"))
    )
    (comp (ref "RS2")
      (value "MECHANICAL-KEYBOARD1.25U")
      (footprint "eagle-import:CHERRY-MX-LED-1.25U")
      (libsource (lib "eagle-import") (part "MECHANICAL-KEYBOARD1.25U"))
    )
    (comp (ref "R_ARR")
      (value "MECHANICAL-KEYBOARD1U")
      (footprint "eagle-import:CHERRY-MX-LED-1U")
      (libsource (lib "eagle-import") (part "MECHANICAL-KEYBOARD1U"))
    )
    (comp (ref "S")
      (value "MECHANICAL-KEYBOARD1U")
      (footprint "eagle-import:CHERRY-MX-LED-1U")
      (libsource (lib "eagle-import") (part "MECHANICAL-KEYBOARD1U"))
    )
    (comp (ref "S1")
      (value "STABILIZER-1X2U")
      (footprint "eagle-import:STABILIZER_1X2U")
      (libsource (lib "eagle-import") (part "STABILIZER-1X2U"))
    )
    (comp (ref "S2")
      (value "STABILIZER-1X2.25U")
      (footprint "eagle-import:STABILIZER_1X2.25U")
      (libsource (lib "eagle-import") (part "STABILIZER-1X2.25U"))
    )
    (comp (ref "S3")
      (value "STABILIZER-1X2.25U")
      (footprint "eagle-import:STABILIZER_1X2.25U")
      (libsource (lib "eagle-import") (part "STABILIZER-1X2.25U"))
    )
    (comp (ref "S4")
      (value "STABILIZER-1X2.75U")
      (footprint "eagle-import:STABILIZER_1X2.75U")
      (libsource (lib "eagle-import") (part "STABILIZER-1X2.75U"))
    )
    (comp (ref "S5")
      (value "STABILIZER-1X6.25U")
      (footprint "eagle-import:STABILIZER_1X6.25U")
      (libsource (lib "eagle-import") (part "STABILIZER-1X6.25U"))
    )
    (comp (ref "SCROLL")
      (value "MECHANICAL-KEYBOARD1U")
      (footprint "eagle-import:CHERRY-MX-LED-1U")
      (libsource (lib "eagle-import") (part "MECHANICAL-KEYBOARD1U"))
    )
    (comp (ref "SPACE")
      (value "MECHANICAL-KEYBOARD6.25U")
      (footprint "eagle-import:CHERRY-MX-LED-1X6.25")
      (libsource (lib "eagle-import") (part "MECHANICAL-KEYBOARD6.25U"))
    )
    (comp (ref "T")
      (value "MECHANICAL-KEYBOARD1U")
      (footprint "eagle-import:CHERRY-MX-LED-1U")
      (libsource (lib "eagle-import") (part "MECHANICAL-KEYBOARD1U"))
    )
    (comp (ref "TAB")
      (value "MECHANICAL-KEYBOARD1.5U")
      (footprint "eagle-import:CHERRY-MX-LED-1.5U")
      (libsource (lib "eagle-import") (part "MECHANICAL-KEYBOARD1.5U"))
    )
    (comp (ref "U")
      (value "MECHANICAL-KEYBOARD1U")
      (footprint "eagle-import:CHERRY-MX-LED-1U")
      (libsource (lib "eagle-import") (part "MECHANICAL-KEYBOARD1U"))
    )
    (comp (ref "UP")
      (value "MECHANICAL-KEYBOARD1U")
      (footprint "eagle-import:CHERRY-MX-LED-1U")
      (libsource (lib "eagle-import") (part "MECHANICAL-KEYBOARD1U"))
    )
    (comp (ref "U_ARR")
      (value "MECHANICAL-KEYBOARD1U")
      (footprint "eagle-import:CHERRY-MX-LED-1U")
      (libsource (lib "eagle-import") (part "MECHANICAL-KEYBOARD1U"))
    )
    (comp (ref "V")
      (value "MECHANICAL-KEYBOARD1U")
      (footprint "eagle-import:CHERRY-MX-LED-1U")
      (libsource (lib "eagle-import") (part "MECHANICAL-KEYBOARD1U"))
    )
    (comp (ref "W")
      (value "MECHANICAL-KEYBOARD1U")
      (footprint "eagle-import:CHERRY-MX-LED-1U")
      (libsource (lib "eagle-import") (part "MECHANICAL-KEYBOARD1U"))
    )
    (comp (ref "X")
      (value "MECHANICAL-KEYBOARD1U")
      (footprint "eagle-import:CHERRY-MX-LED-1U")
      (libsource (lib "eagle-import") (part "MECHANICAL-KEYBOARD1U"))
    )
    (comp (ref "Y/Z")
      (value "MECHANICAL-KEYBOARD1U")
      (footprint "eagle-import:CHERRY-MX-LED-1U")
      (libsource (lib "eagle-import") (part "MECHANICAL-KEYBOARD1U"))
    )
    (comp (ref "Z/Y")
      (value "MECHANICAL-KEYBOARD1U")
      (footprint "eagle-import:CHERRY-MX-LED-1U")
      (libsource (lib "eagle-import") (part "MECHANICAL-KEYBOARD1U"))
    )
    (comp (ref "[/Ü")
      (value "MECHANICAL-KEYBOARD1U")
      (footprint "eagle-import:CHERRY-MX-LED-1U")
      (libsource (lib "eagle-import") (part "MECHANICAL-KEYBOARD1U"))
    )
    (comp (ref "\\\\/#")
      (value "MECHANICAL-KEYBOARD1.5U")
      (footprint "eagle-import:CHERRY-MX-LED-1.5U")
      (libsource (lib "eagle-import") (part "MECHANICAL-KEYBOARD1.5U"))
    )
    (comp (ref "]/+")
      (value "MECHANICAL-KEYBOARD1U")
      (footprint "eagle-import:CHERRY-MX-LED-1U")
      (libsource (lib "eagle-import") (part "MECHANICAL-KEYBOARD1U"))
    )
    (comp (ref "`/^")
      (value "MECHANICAL-KEYBOARD1U")
      (footprint "eagle-import:CHERRY-MX-LED-1U")
      (libsource (lib "eagle-import") (part "MECHANICAL-KEYBOARD1U"))
    )
    (comp (ref "C1")
      (value "10n 100V")
      (footprint "eagle-import:C0603")
      (libsource (lib "eagle-import") (part "C-EUC0603"))
    )
    (comp (ref "C2")
      (value "100nF")
      (footprint "eagle-import:C0603")
      (libsource (lib "eagle-import") (part "C-EUC0603"))
    )
    (comp (ref "C3")
      (value "100uF")
      (footprint "eagle-import:CT3528")
      (libsource (lib "eagle-import") (part "CPOL-EUCT3528"))
    )
    (comp (ref "C4")
      (value "10n 100V")
      (footprint "eagle-import:C0603")
      (libsource (lib "eagle-import") (part "C-EUC0603"))
    )
    (comp (ref "C5")
      (value "100uF")
      (footprint "eagle-import:CT3528")
      (libsource (lib "eagle-import") (part "CPOL-EUCT3528"))
    )
    (comp (ref "C6")
      (value "10n 100V")
      (footprint "eagle-import:C0603")
      (libsource (lib "eagle-import") (part "C-EUC0603"))
    )
    (comp (ref "C7")
      (value "100uF")
      (footprint "eagle-import:CT3528")
      (libsource (lib "eagle-import") (part "CPOL-EUCT3528"))
    )
    (comp (ref "C8")
      (value "10n 100V")
      (footprint "eagle-import:C0603")
      (libsource (lib "eagle-import") (part "C-EUC0603"))
    )
    (comp (ref "C9")
      (value "12pF")
      (footprint "eagle-import:C0603")
      (libsource (lib "eagle-import") (part "C-EUC0603"))
    )
    (comp (ref "C10")
      (value "100nF")
      (footprint "eagle-import:C0603")
      (libsource (lib "eagle-import") (part "C-EUC0603"))
    )
    (comp (ref "C11")
      (value "10u")
      (footprint "eagle-import:C0603")
      (libsource (lib "eagle-import") (part "C-EUC0603"))
    )
    (comp (ref "C12")
      (value "10u")
      (footprint "eagle-import:C0603")
      (libsource (lib "eagle-import") (part "C-EUC0603"))
    )
    (comp (ref "C13")
      (value "10u")
      (footprint "eagle-import:C0603")
      (libsource (lib "eagle-import") (part "C-EUC0603"))
    )
    (comp (ref "C14")
      (value "10n")
      (footprint "eagle-import:C0603")
      (libsource (lib "eagle-import") (part "C-EUC0603"))
    )
    (comp (ref "C15")
      (value "100nF")
      (footprint "eagle-import:C0603")
      (libsource (lib "eagle-import") (part "C-EUC0603"))
    )
    (comp (ref "C16")
      (value "12pF")
      (footprint "eagle-import:C0603")
      (libsource (lib "eagle-import") (part "C-EUC0603"))
    )
    (comp (ref "C17")
      (value "12pF")
      (footprint "eagle-import:C0603")
      (libsource (lib "eagle-import") (part "C-EUC0603"))
    )
    (comp (ref "C18")
      (value "12pF")
      (footprint "eagle-import:C0603")
      (libsource (lib "eagle-import") (part "C-EUC0603"))
    )
    (comp (ref "C19")
      (value "100nF")
      (footprint "eagle-import:C0603")
      (libsource (lib "eagle-import") (part "C-EUC0603"))
    )
    (comp (ref "C20")
      (value "1u")
      (footprint "eagle-import:C0603")
      (libsource (lib "eagle-import") (part "C-EUC0603"))
    )
    (comp (ref "D14")
      (value "PRTR5V0U2X")
      (footprint "eagle-import:SOT143")
      (libsource (lib "eagle-import") (part "PRTR5V0U2X"))
    )
    (comp (ref "D16")
      (value "PRTR5V0U2X")
      (footprint "eagle-import:SOT143")
      (libsource (lib "eagle-import") (part "PRTR5V0U2X"))
    )
    (comp (ref "D18")
      (value "PRTR5V0U2X")
      (footprint "eagle-import:SOT143")
      (libsource (lib "eagle-import") (part "PRTR5V0U2X"))
    )
    (comp (ref "DISPLAY")
      (value "I2C_OLED_128X32")
      (footprint "eagle-import:128X32_I2C_OLED")
      (libsource (lib "eagle-import") (part "I2C_OLED_128X32"))
    )
    (comp (ref "F1")
      (value "1.1A Hold")
      (footprint "eagle-import:R1210")
      (libsource (lib "eagle-import") (part "R-EU_R1210"))
    )
    (comp (ref "IC1")
      (value "FE1.1S")
      (footprint "eagle-import:SSOP28")
      (libsource (lib "eagle-import") (part "FE1.1S"))
    )
    (comp (ref "IC2")
      (value "24LC024SN")
      (footprint "eagle-import:SO-08")
      (fields (field (name "MF") "MICROCHIP") (field (name "MPN") "24LC024/SN"))
      (libsource (lib "eagle-import") (part "24SNLC024"))
    )
    (comp (ref "IC3")
      (value "PCF8574APWR")
      (footprint "eagle-import:SSOP20")
      (fields (field (name "MPN") "PCF8574TS/3,118"))
      (libsource (lib "eagle-import") (part "PCF8574TS"))
    )
    (comp (ref "IC4")
      (value "ATMEGA32U4-MU")
      (footprint "eagle-import:QFN44G-0.5-7X7MM")
      (fields (field (name "MF") "Microchip") (field (name "MP") "ATMEGA32U4-MUR"))
      (libsource (lib "eagle-import") (part "MCU-ATMEGA32U4-MUR(VQFN44)"))
    )
    (comp (ref "ISP")
      (value "AVR-ISP-6-EDGE")
      (footprint "eagle-import:6PAD_ISP")
      (libsource (lib "eagle-import") (part "AVR-ISP-6-EDGE"))
    )
    (comp (ref "J1")
      (value "USB_A_SMT_FEMALE")
      (footprint "eagle-import:USB-A-S-SILK-FEMALE")
      (libsource (lib "eagle-import") (part "USB_A_SMT_FEMALE"))
    )
    (comp (ref "J2")
      (value "USB_A_SMT_FEMALE")
      (footprint "eagle-import:USB-A-S-SILK-FEMALE")
      (libsource (lib "eagle-import") (part "USB_A_SMT_FEMALE"))
    )
    (comp (ref "J3")
      (value "USB_A_SMT_FEMALE")
      (footprint "eagle-import:USB-A-S-SILK-FEMALE")
      (libsource (lib "eagle-import") (part "USB_A_SMT_FEMALE"))
    )
    (comp (ref "J4")
      (value "USB_C2-LAYER")
      (footprint "eagle-import:USB-C-16P")
      (libsource (lib "eagle-import") (part "USB_C2-LAYER"))
    )
    (comp (ref "LED1")
      (value "LED3MM")
      (footprint "eagle-import:LED3MM")
      (libsource (lib "eagle-import") (part "LED3MM"))
    )
    (comp (ref "LED2")
      (value "LED3MM")
      (footprint "eagle-import:LED3MM")
      (libsource (lib "eagle-import") (part "LED3MM"))
    )
    (comp (ref "LED3")
      (value "LED3MM")
      (footprint "eagle-import:LED3MM")
      (libsource (lib "eagle-import") (part "LED3MM"))
    )
    (comp (ref "LED4")
      (value "LED3MM")
      (footprint "eagle-import:LED3MM")
      (libsource (lib "eagle-import") (part "LED3MM"))
    )
    (comp (ref "LED5")
      (value "LED3MM")
      (footprint "eagle-import:LED3MM")
      (libsource (lib "eagle-import") (part "LED3MM"))
    )
    (comp (ref "LED6")
      (value "LED3MM")
      (footprint "eagle-import:LED3MM")
      (libsource (lib "eagle-import") (part "LED3MM"))
    )
    (comp (ref "R1")
      (value "2k7")
      (footprint "eagle-import:R0603")
      (libsource (lib "eagle-import") (part "R-EU_R0603"))
    )
    (comp (ref "R2")
      (value "5k1")
      (footprint "eagle-import:R0603")
      (libsource (lib "eagle-import") (part "R-EU_R0603"))
    )
    (comp (ref "R3")
      (value "22R")
      (footprint "eagle-import:R0603")
      (libsource (lib "eagle-import") (part "R-EU_R0603"))
    )
    (comp (ref "R4")
      (value "22R")
      (footprint "eagle-import:R0603")
      (libsource (lib "eagle-import") (part "R-EU_R0603"))
    )
    (comp (ref "R5")
      (value "20k")
      (footprint "eagle-import:R0603")
      (libsource (lib "eagle-import") (part "R-EU_R0603"))
    )
    (comp (ref "R6")
      (value "5k1")
      (footprint "eagle-import:R0603")
      (libsource (lib "eagle-import") (part "R-EU_R0603"))
    )
    (comp (ref "R7")
      (value "10k")
      (footprint "eagle-import:R0603")
      (libsource (lib "eagle-import") (part "R-EU_R0603"))
    )
    (comp (ref "R8")
      (value "1M")
      (footprint "eagle-import:R0603")
      (libsource (lib "eagle-import") (part "R-EU_R0603"))
    )
    (comp (ref "R9")
      (value "Ferrite 2A")
      (footprint "eagle-import:R0805")
      (libsource (lib "eagle-import") (part "R-EU_R0805"))
    )
    (comp (ref "R10")
      (value "1M")
      (footprint "eagle-import:R0603")
      (libsource (lib "eagle-import") (part "R-EU_R0603"))
    )
    (comp (ref "R11")
      (value "22R")
      (footprint "eagle-import:R0603")
      (libsource (lib "eagle-import") (part "R-EU_R0603"))
    )
    (comp (ref "R12")
      (value "22R")
      (footprint "eagle-import:R0603")
      (libsource (lib "eagle-import") (part "R-EU_R0603"))
    )
    (comp (ref "R13")
      (value "1M")
      (footprint "eagle-import:R0603")
      (libsource (lib "eagle-import") (part "R-EU_R0603"))
    )
    (comp (ref "R14")
      (value "22R")
      (footprint "eagle-import:R0603")
      (libsource (lib "eagle-import") (part "R-EU_R0603"))
    )
    (comp (ref "R15")
      (value "22R")
      (footprint "eagle-import:R0603")
      (libsource (lib "eagle-import") (part "R-EU_R0603"))
    )
    (comp (ref "R16")
      (value "1M")
      (footprint "eagle-import:R0603")
      (libsource (lib "eagle-import") (part "R-EU_R0603"))
    )
    (comp (ref "R17")
      (value "22R")
      (footprint "eagle-import:R0603")
      (libsource (lib "eagle-import") (part "R-EU_R0603"))
    )
    (comp (ref "R18")
      (value "22R")
      (footprint "eagle-import:R0603")
      (libsource (lib "eagle-import") (part "R-EU_R0603"))
    )
    (comp (ref "R19")
      (value "100k")
      (footprint "eagle-import:R0603")
      (libsource (lib "eagle-import") (part "R-EU_R0603"))
    )
    (comp (ref "R20")
      (value "10k")
      (footprint "eagle-import:R0603")
      (libsource (lib "eagle-import") (part "R-EU_R0603"))
    )
    (comp (ref "R21")
      (value "10k")
      (footprint "eagle-import:R0603")
      (libsource (lib "eagle-import") (part "R-EU_R0603"))
    )
    (comp (ref "R22")
      (value "1k")
      (footprint "eagle-import:R0603")
      (libsource (lib "eagle-import") (part "R-EU_R0603"))
    )
    (comp (ref "R23")
      (value "1k")
      (footprint "eagle-import:R0603")
      (libsource (lib "eagle-import") (part "R-EU_R0603"))
    )
    (comp (ref "R24")
      (value "20k")
      (footprint "eagle-import:R0603")
      (libsource (lib "eagle-import") (part "R-EU_R0603"))
    )
    (comp (ref "R25")
      (value "20k")
      (footprint "eagle-import:R0603")
      (libsource (lib "eagle-import") (part "R-EU_R0603"))
    )
    (comp (ref "R26")
      (value "1k")
      (footprint "eagle-import:R0603")
      (libsource (lib "eagle-import") (part "R-EU_R0603"))
    )
    (comp (ref "R27")
      (value "1k")
      (footprint "eagle-import:R0603")
      (libsource (lib "eagle-import") (part "R-EU_R0603"))
    )
    (comp (ref "R28")
      (value "1k")
      (footprint "eagle-import:R0603")
      (libsource (lib "eagle-import") (part "R-EU_R0603"))
    )
    (comp (ref "R29")
      (value "1k")
      (footprint "eagle-import:R0603")
      (libsource (lib "eagle-import") (part "R-EU_R0603"))
    )
    (comp (ref "R30")
      (value "1k")
      (footprint "eagle-import:R0603")
      (libsource (lib "eagle-import") (part "R-EU_R0603"))
    )
    (comp (ref "R31")
      (value "1k")
      (footprint "eagle-import:R0603")
      (libsource (lib "eagle-import") (part "R-EU_R0603"))
    )
    (comp (ref "R32")
      (value "1k")
      (footprint "eagle-import:R0603")
      (libsource (lib "eagle-import") (part "R-EU_R0603"))
    )
    (comp (ref "R33")
      (value "10k")
      (footprint "eagle-import:R0603")
      (libsource (lib "eagle-import") (part "R-EU_R0603"))
    )
    (comp (ref "RESET")
      (value "MOMENTARY-SWITCH-SPST-SMD-5.2-REDUNDANT")
      (footprint "eagle-import:TACTILE_SWITCH_SMD_5.2MM")
      (libsource (lib "eagle-import") (part "MOMENTARY-SWITCH-SPST-SMD-5.2-REDUNDANT"))
    )
    (comp (ref "X1")
      (value "12MHz")
      (footprint "eagle-import:3.2X2.5_KX-7")
      (libsource (lib "eagle-import") (part "KX-7"))
    )
    (comp (ref "X2")
      (value "16MHz")
      (footprint "eagle-import:3.2X2.5_KX-7")
      (libsource (lib "eagle-import") (part "KX-7"))
    )
  )
  (nets
    (net (code "1") (name "1V8_HUB") (class "Default")
      (node (ref "C11") (pin "2") (pinfunction "2_2") (pintype "passive"))
      (node (ref "C15") (pin "2") (pinfunction "2_2") (pintype "passive"))
      (node (ref "IC1") (pin "12") (pinfunction "VD18_O_12") (pintype "power_in"))
      (node (ref "IC1") (pin "28") (pinfunction "VD18_28") (pintype "power_in"))
    )
    (net (code "2") (name "3V3_HUB") (class "Default")
      (node (ref "C10") (pin "2") (pinfunction "2_2") (pintype "passive"))
      (node (ref "C13") (pin "2") (pinfunction "2_2") (pintype "passive"))
      (node (ref "IC1") (pin "13") (pinfunction "VD33_13") (pintype "power_in"))
      (node (ref "IC1") (pin "21") (pinfunction "VVD33_O_21") (pintype "power_in"))
      (node (ref "IC2") (pin "7") (pinfunction "WP_7") (pintype "input"))
      (node (ref "IC2") (pin "8") (pinfunction "VCC_8") (pintype "power_in"))
      (node (ref "R5") (pin "1") (pinfunction "1_1") (pintype "passive"))
    )
    (net (code "3") (name "C1") (class "Default")
      (node (ref "D1") (pin "C") (pinfunction "C_C") (pintype "passive"))
      (node (ref "D20") (pin "C") (pinfunction "C_C") (pintype "passive"))
      (node (ref "D37") (pin "C") (pinfunction "C_C") (pintype "passive"))
      (node (ref "D54") (pin "C") (pinfunction "C_C") (pintype "passive"))
      (node (ref "D67") (pin "C") (pinfunction "C_C") (pintype "passive"))
      (node (ref "D81") (pin "C") (pinfunction "C_C") (pintype "passive"))
      (node (ref "IC4") (pin "8") (pinfunction "PB0(SS/PCINT0)_8") (pintype "bidirectional"))
    )
    (net (code "4") (name "C2{slash}SCK") (class "Default")
      (node (ref "D21") (pin "C") (pinfunction "C_C") (pintype "passive"))
      (node (ref "D38") (pin "C") (pinfunction "C_C") (pintype "passive"))
      (node (ref "D55") (pin "C") (pinfunction "C_C") (pintype "passive"))
      (node (ref "D68") (pin "C") (pinfunction "C_C") (pintype "passive"))
      (node (ref "D82") (pin "C") (pinfunction "C_C") (pintype "passive"))
      (node (ref "IC4") (pin "9") (pinfunction "PB1(PCINT1/SCLK)_9") (pintype "bidirectional"))
      (node (ref "ISP") (pin "SCK") (pinfunction "P$2_SCK") (pintype "bidirectional"))
    )
    (net (code "5") (name "C3{slash}MOSI") (class "Default")
      (node (ref "D2") (pin "C") (pinfunction "C_C") (pintype "passive"))
      (node (ref "D22") (pin "C") (pinfunction "C_C") (pintype "passive"))
      (node (ref "D39") (pin "C") (pinfunction "C_C") (pintype "passive"))
      (node (ref "D56") (pin "C") (pinfunction "C_C") (pintype "passive"))
      (node (ref "D69") (pin "C") (pinfunction "C_C") (pintype "passive"))
      (node (ref "D83") (pin "C") (pinfunction "C_C") (pintype "passive"))
      (node (ref "IC4") (pin "10") (pinfunction "PB2(PDI/PCINT2/MOSI)_10") (pintype "bidirectional"))
      (node (ref "ISP") (pin "MOSI") (pinfunction "P$5_MOSI") (pintype "bidirectional"))
    )
    (net (code "6") (name "C4{slash}MISO") (class "Default")
      (node (ref "D23") (pin "C") (pinfunction "C_C") (pintype "passive"))
      (node (ref "D3") (pin "C") (pinfunction "C_C") (pintype "passive"))
      (node (ref "D40") (pin "C") (pinfunction "C_C") (pintype "passive"))
      (node (ref "D57") (pin "C") (pinfunction "C_C") (pintype "passive"))
      (node (ref "D70") (pin "C") (pinfunction "C_C") (pintype "passive"))
      (node (ref "D84") (pin "C") (pinfunction "C_C") (pintype "passive"))
      (node (ref "IC4") (pin "11") (pinfunction "PB3(PD0/PCINT3/MISO)_11") (pintype "bidirectional"))
      (node (ref "ISP") (pin "MISO") (pinfunction "P$1_MISO") (pintype "bidirectional"))
    )
    (net (code "7") (name "C5") (class "Default")
      (node (ref "D24") (pin "C") (pinfunction "C_C") (pintype "passive"))
      (node (ref "D4") (pin "C") (pinfunction "C_C") (pintype "passive"))
      (node (ref "D41") (pin "C") (pinfunction "C_C") (pintype "passive"))
      (node (ref "D58") (pin "C") (pinfunction "C_C") (pintype "passive"))
      (node (ref "D71") (pin "C") (pinfunction "C_C") (pintype "passive"))
      (node (ref "D85") (pin "C") (pinfunction "C_C") (pintype "passive"))
      (node (ref "IC4") (pin "12") (pinfunction "PB7(PCINT7/OC0A/OC1C/~{RTS})_12") (pintype "bidirectional"))
    )
    (net (code "8") (name "C6") (class "Default")
      (node (ref "D15") (pin "C") (pinfunction "C_C") (pintype "passive"))
      (node (ref "D25") (pin "C") (pinfunction "C_C") (pintype "passive"))
      (node (ref "D42") (pin "C") (pinfunction "C_C") (pintype "passive"))
      (node (ref "D59") (pin "C") (pinfunction "C_C") (pintype "passive"))
      (node (ref "D72") (pin "C") (pinfunction "C_C") (pintype "passive"))
      (node (ref "IC4") (pin "20") (pinfunction "PD2(RXD1/INT2)_20") (pintype "bidirectional"))
    )
    (net (code "9") (name "C7") (class "Default")
      (node (ref "D26") (pin "C") (pinfunction "C_C") (pintype "passive"))
      (node (ref "D43") (pin "C") (pinfunction "C_C") (pintype "passive"))
      (node (ref "D5") (pin "C") (pinfunction "C_C") (pintype "passive"))
      (node (ref "D60") (pin "C") (pinfunction "C_C") (pintype "passive"))
      (node (ref "D73") (pin "C") (pinfunction "C_C") (pintype "passive"))
      (node (ref "D86") (pin "C") (pinfunction "C_C") (pintype "passive"))
      (node (ref "IC4") (pin "21") (pinfunction "PD3(TXD1/INT3)_21") (pintype "bidirectional"))
    )
    (net (code "10") (name "C8") (class "Default")
      (node (ref "D27") (pin "C") (pinfunction "C_C") (pintype "passive"))
      (node (ref "D44") (pin "C") (pinfunction "C_C") (pintype "passive"))
      (node (ref "D6") (pin "C") (pinfunction "C_C") (pintype "passive"))
      (node (ref "D61") (pin "C") (pinfunction "C_C") (pintype "passive"))
      (node (ref "D74") (pin "C") (pinfunction "C_C") (pintype "passive"))
      (node (ref "D87") (pin "C") (pinfunction "C_C") (pintype "passive"))
      (node (ref "IC4") (pin "22") (pinfunction "PD5(XCLK1/~{CTS})_22") (pintype "bidirectional"))
    )
    (net (code "11") (name "C9") (class "Default")
      (node (ref "D28") (pin "C") (pinfunction "C_C") (pintype "passive"))
      (node (ref "D45") (pin "C") (pinfunction "C_C") (pintype "passive"))
      (node (ref "D62") (pin "C") (pinfunction "C_C") (pintype "passive"))
      (node (ref "D7") (pin "C") (pinfunction "C_C") (pintype "passive"))
      (node (ref "D75") (pin "C") (pinfunction "C_C") (pintype "passive"))
      (node (ref "D88") (pin "C") (pinfunction "C_C") (pintype "passive"))
      (node (ref "IC4") (pin "25") (pinfunction "PD4(ICP1/ADC8)_25") (pintype "bidirectional"))
    )
    (net (code "12") (name "C10") (class "Default")
      (node (ref "D17") (pin "C") (pinfunction "C_C") (pintype "passive"))
      (node (ref "D29") (pin "C") (pinfunction "C_C") (pintype "passive"))
      (node (ref "D46") (pin "C") (pinfunction "C_C") (pintype "passive"))
      (node (ref "D63") (pin "C") (pinfunction "C_C") (pintype "passive"))
      (node (ref "D76") (pin "C") (pinfunction "C_C") (pintype "passive"))
      (node (ref "D89") (pin "C") (pinfunction "C_C") (pintype "passive"))
      (node (ref "IC4") (pin "26") (pinfunction "PD6(T1/ADC9/~{OC4D})_26") (pintype "bidirectional"))
    )
    (net (code "13") (name "C11") (class "Default")
      (node (ref "D30") (pin "C") (pinfunction "C_C") (pintype "passive"))
      (node (ref "D47") (pin "C") (pinfunction "C_C") (pintype "passive"))
      (node (ref "D64") (pin "C") (pinfunction "C_C") (pintype "passive"))
      (node (ref "D77") (pin "C") (pinfunction "C_C") (pintype "passive"))
      (node (ref "D8") (pin "C") (pinfunction "C_C") (pintype "passive"))
      (node (ref "D90") (pin "C") (pinfunction "C_C") (pintype "passive"))
      (node (ref "IC4") (pin "27") (pinfunction "PD7(T0/OC4D/ADC10)_27") (pintype "bidirectional"))
    )
    (net (code "14") (name "C12") (class "Default")
      (node (ref "D31") (pin "C") (pinfunction "C_C") (pintype "passive"))
      (node (ref "D48") (pin "C") (pinfunction "C_C") (pintype "passive"))
      (node (ref "D65") (pin "C") (pinfunction "C_C") (pintype "passive"))
      (node (ref "D78") (pin "C") (pinfunction "C_C") (pintype "passive"))
      (node (ref "D9") (pin "C") (pinfunction "C_C") (pintype "passive"))
      (node (ref "IC4") (pin "28") (pinfunction "PB4(PCINT4/ADC11)_28") (pintype "bidirectional"))
    )
    (net (code "15") (name "C13") (class "Default")
      (node (ref "D10") (pin "C") (pinfunction "C_C") (pintype "passive"))
      (node (ref "D32") (pin "C") (pinfunction "C_C") (pintype "passive"))
      (node (ref "D49") (pin "C") (pinfunction "C_C") (pintype "passive"))
      (node (ref "D91") (pin "C") (pinfunction "C_C") (pintype "passive"))
      (node (ref "IC4") (pin "29") (pinfunction "PB5(PCINT5/OC1A/ADC12/~{OC4B})_29") (pintype "bidirectional"))
    )
    (net (code "16") (name "C14") (class "Default")
      (node (ref "D19") (pin "C") (pinfunction "C_C") (pintype "passive"))
      (node (ref "D33") (pin "C") (pinfunction "C_C") (pintype "passive"))
      (node (ref "D50") (pin "C") (pinfunction "C_C") (pintype "passive"))
      (node (ref "D66") (pin "C") (pinfunction "C_C") (pintype "passive"))
      (node (ref "D79") (pin "C") (pinfunction "C_C") (pintype "passive"))
      (node (ref "D92") (pin "C") (pinfunction "C_C") (pintype "passive"))
      (node (ref "IC4") (pin "30") (pinfunction "PB6(PCINT6/OC1B/OC4B/ADC13)_30") (pintype "bidirectional"))
    )
    (net (code "17") (name "C15") (class "Default")
      (node (ref "D11") (pin "C") (pinfunction "C_C") (pintype "passive"))
      (node (ref "D34") (pin "C") (pinfunction "C_C") (pintype "passive"))
      (node (ref "D51") (pin "C") (pinfunction "C_C") (pintype "passive"))
      (node (ref "D93") (pin "C") (pinfunction "C_C") (pintype "passive"))
      (node (ref "IC4") (pin "31") (pinfunction "PC6(OC3A/~{OC4A})_31") (pintype "bidirectional"))
    )
    (net (code "18") (name "C16") (class "Default")
      (node (ref "D12") (pin "C") (pinfunction "C_C") (pintype "passive"))
      (node (ref "D35") (pin "C") (pinfunction "C_C") (pintype "passive"))
      (node (ref "D52") (pin "C") (pinfunction "C_C") (pintype "passive"))
      (node (ref "D80") (pin "C") (pinfunction "C_C") (pintype "passive"))
      (node (ref "D94") (pin "C") (pinfunction "C_C") (pintype "passive"))
      (node (ref "IC4") (pin "32") (pinfunction "PC7(ICP3/CLK0/OC4A)_32") (pintype "bidirectional"))
    )
    (net (code "19") (name "C17") (class "Default")
      (node (ref "D13") (pin "C") (pinfunction "C_C") (pintype "passive"))
      (node (ref "D36") (pin "C") (pinfunction "C_C") (pintype "passive"))
      (node (ref "D53") (pin "C") (pinfunction "C_C") (pintype "passive"))
      (node (ref "D95") (pin "C") (pinfunction "C_C") (pintype "passive"))
      (node (ref "IC4") (pin "1") (pinfunction "PE6(INT.6/AIN0)_1") (pintype "bidirectional"))
    )
    (net (code "20") (name "CL_LED_A") (class "Default")
      (node (ref "CAPSLOCK") (pin "A") (pinfunction "A_A") (pintype "passive"))
      (node (ref "R22") (pin "1") (pinfunction "1_1") (pintype "passive"))
    )
    (net (code "21") (name "CL_LED_C") (class "Default")
      (node (ref "CAPSLOCK") (pin "K") (pinfunction "C_K") (pintype "passive"))
      (node (ref "IC3") (pin "11") (pinfunction "P1_11") (pintype "bidirectional"))
    )
    (net (code "22") (name "GND") (class "Default")
      (node (ref "C1") (pin "1") (pinfunction "1_1") (pintype "passive"))
      (node (ref "C10") (pin "1") (pinfunction "1_1") (pintype "passive"))
      (node (ref "C11") (pin "1") (pinfunction "1_1") (pintype "passive"))
      (node (ref "C12") (pin "1") (pinfunction "1_1") (pintype "passive"))
      (node (ref "C13") (pin "1") (pinfunction "1_1") (pintype "passive"))
      (node (ref "C14") (pin "1") (pinfunction "1_1") (pintype "passive"))
      (node (ref "C15") (pin "1") (pinfunction "1_1") (pintype "passive"))
      (node (ref "C16") (pin "2") (pinfunction "2_2") (pintype "passive"))
      (node (ref "C17") (pin "2") (pinfunction "2_2") (pintype "passive"))
      (node (ref "C18") (pin "2") (pinfunction "2_2") (pintype "passive"))
      (node (ref "C19") (pin "1") (pinfunction "1_1") (pintype "passive"))
      (node (ref "C2") (pin "1") (pinfunction "1_1") (pintype "passive"))
      (node (ref "C20") (pin "1") (pinfunction "1_1") (pintype "passive"))
      (node (ref "C3") (pin "-") (pinfunction "-_-") (pintype "passive"))
      (node (ref "C4") (pin "1") (pinfunction "1_1") (pintype "passive"))
      (node (ref "C5") (pin "-") (pinfunction "-_-") (pintype "passive"))
      (node (ref "C6") (pin "1") (pinfunction "1_1") (pintype "passive"))
      (node (ref "C7") (pin "-") (pinfunction "-_-") (pintype "passive"))
      (node (ref "C8") (pin "1") (pinfunction "1_1") (pintype "passive"))
      (node (ref "C9") (pin "2") (pinfunction "2_2") (pintype "passive"))
      (node (ref "D14") (pin "1") (pinfunction "GND_1") (pintype "passive"))
      (node (ref "D16") (pin "1") (pinfunction "GND_1") (pintype "passive"))
      (node (ref "D18") (pin "1") (pinfunction "GND_1") (pintype "passive"))
      (node (ref "DISPLAY") (pin "1") (pinfunction "GND_1") (pintype "passive"))
      (node (ref "IC1") (pin "1") (pinfunction "VSS_1") (pintype "power_in"))
      (node (ref "IC2") (pin "1") (pinfunction "A0_1") (pintype "input"))
      (node (ref "IC2") (pin "2") (pinfunction "A1_2") (pintype "input"))
      (node (ref "IC2") (pin "3") (pinfunction "A2_3") (pintype "input"))
      (node (ref "IC2") (pin "4") (pinfunction "GND_4") (pintype "power_in"))
      (node (ref "IC3") (pin "15") (pinfunction "VSS_15") (pintype "power_in"))
      (node (ref "IC3") (pin "6") (pinfunction "A0_6") (pintype "input"))
      (node (ref "IC3") (pin "7") (pinfunction "A1_7") (pintype "input"))
      (node (ref "IC3") (pin "9") (pinfunction "A2_9") (pintype "input"))
      (node (ref "IC4") (pin "15") (pinfunction "GND_15") (pintype "bidirectional"))
      (node (ref "IC4") (pin "23") (pinfunction "GND_23") (pintype "bidirectional"))
      (node (ref "IC4") (pin "35") (pinfunction "GND_35") (pintype "bidirectional"))
      (node (ref "IC4") (pin "43") (pinfunction "GND_43") (pintype "bidirectional"))
      (node (ref "IC4") (pin "5") (pinfunction "UGND_5") (pintype "bidirectional"))
      (node (ref "IC4") (pin "TAB") (pinfunction "GND_TAB") (pintype "bidirectional"))
      (node (ref "ISP") (pin "GND") (pinfunction "P$4_GND") (pintype "bidirectional"))
      (node (ref "J1") (pin "GND") (pinfunction "GND_GND") (pintype "power_in"))
      (node (ref "J2") (pin "GND") (pinfunction "GND_GND") (pintype "power_in"))
      (node (ref "J3") (pin "GND") (pinfunction "GND_GND") (pintype "power_in"))
      (node (ref "J4") (pin "GND") (pinfunction "GND_GND") (pintype "bidirectional"))
      (node (ref "J4") (pin "GND2") (pinfunction "GND_GND2") (pintype "bidirectional"))
      (node (ref "R1") (pin "1") (pinfunction "1_1") (pintype "passive"))
      (node (ref "R10") (pin "2") (pinfunction "2_2") (pintype "passive"))
      (node (ref "R13") (pin "2") (pinfunction "2_2") (pintype "passive"))
      (node (ref "R16") (pin "2") (pinfunction "2_2") (pintype "passive"))
      (node (ref "R19") (pin "1") (pinfunction "1_1") (pintype "passive"))
      (node (ref "R2") (pin "1") (pinfunction "1_1") (pintype "passive"))
      (node (ref "R20") (pin "2") (pinfunction "2_2") (pintype "passive"))
      (node (ref "R26") (pin "1") (pinfunction "1_1") (pintype "passive"))
      (node (ref "R6") (pin "1") (pinfunction "1_1") (pintype "passive"))
      (node (ref "R8") (pin "2") (pinfunction "2_2") (pintype "passive"))
      (node (ref "RESET") (pin "3") (pinfunction "2_3") (pintype "passive"))
      (node (ref "RESET") (pin "4") (pinfunction "2_4") (pintype "passive"))
    )
    (net (code "23") (name "Net-(,/Ä-2)") (class "Default")
      (node (ref ",/Ä") (pin "S2") (pinfunction "2_S2") (pintype "passive"))
      (node (ref "D65") (pin "A") (pinfunction "A_A") (pintype "passive"))
    )
    (net (code "24") (name "Net-(-/ß-2)") (class "Default")
      (node (ref "-/ß") (pin "S2") (pinfunction "2_S2") (pintype "passive"))
      (node (ref "D31") (pin "A") (pinfunction "A_A") (pintype "passive"))
    )
    (net (code "25") (name "Net-(.-2)") (class "Default")
      (node (ref ".") (pin "S2") (pinfunction "2_S2") (pintype "passive"))
      (node (ref "D64") (pin "A") (pinfunction "A_A") (pintype "passive"))
    )
    (net (code "26") (name "Net-(//--2)") (class "Default")
      (node (ref "//-") (pin "S2") (pinfunction "2_S2") (pintype "passive"))
      (node (ref "D78") (pin "A") (pinfunction "A_A") (pintype "passive"))
    )
    (net (code "27") (name "Net-(0-2)") (class "Default")
      (node (ref "0") (pin "S2") (pinfunction "2_S2") (pintype "passive"))
      (node (ref "D30") (pin "A") (pinfunction "A_A") (pintype "passive"))
    )
    (net (code "28") (name "Net-(1-2)") (class "Default")
      (node (ref "1") (pin "S2") (pinfunction "2_S2") (pintype "passive"))
      (node (ref "D21") (pin "A") (pinfunction "A_A") (pintype "passive"))
    )
    (net (code "29") (name "Net-(2-2)") (class "Default")
      (node (ref "2") (pin "S2") (pinfunction "2_S2") (pintype "passive"))
      (node (ref "D22") (pin "A") (pinfunction "A_A") (pintype "passive"))
    )
    (net (code "30") (name "Net-(3-2)") (class "Default")
      (node (ref "3") (pin "S2") (pinfunction "2_S2") (pintype "passive"))
      (node (ref "D23") (pin "A") (pinfunction "A_A") (pintype "passive"))
    )
    (net (code "31") (name "Net-(4-2)") (class "Default")
      (node (ref "4") (pin "S2") (pinfunction "2_S2") (pintype "passive"))
      (node (ref "D24") (pin "A") (pinfunction "A_A") (pintype "passive"))
    )
    (net (code "32") (name "Net-(5-2)") (class "Default")
      (node (ref "5") (pin "S2") (pinfunction "2_S2") (pintype "passive"))
      (node (ref "D25") (pin "A") (pinfunction "A_A") (pintype "passive"))
    )
    (net (code "33") (name "Net-(6-2)") (class "Default")
      (node (ref "6") (pin "S2") (pinfunction "2_S2") (pintype "passive"))
      (node (ref "D26") (pin "A") (pinfunction "A_A") (pintype "passive"))
    )
    (net (code "34") (name "Net-(7-2)") (class "Default")
      (node (ref "7") (pin "S2") (pinfunction "2_S2") (pintype "passive"))
      (node (ref "D27") (pin "A") (pinfunction "A_A") (pintype "passive"))
    )
    (net (code "35") (name "Net-(8-2)") (class "Default")
      (node (ref "8") (pin "S2") (pinfunction "2_S2") (pintype "passive"))
      (node (ref "D28") (pin "A") (pinfunction "A_A") (pintype "passive"))
    )
    (net (code "36") (name "Net-(9-2)") (class "Default")
      (node (ref "9") (pin "S2") (pinfunction "2_S2") (pintype "passive"))
      (node (ref "D29") (pin "A") (pinfunction "A_A") (pintype "passive"))
    )
    (net (code "37") (name "Net-(</,-2)") (class "Default")
      (node (ref "</,") (pin "S2") (pinfunction "2_S2") (pintype "passive"))
      (node (ref "D76") (pin "A") (pinfunction "A_A") (pintype "passive"))
    )
    (net (code "38") (name "Net-(<>-2)") (class "Default")
      (node (ref "<>") (pin "S2") (pinfunction "2_S2") (pintype "passive"))
      (node (ref "D68") (pin "A") (pinfunction "A_A") (pintype "passive"))
    )
    (net (code "39") (name "Net-(=/´-2)") (class "Default")
      (node (ref "=/´") (pin "S2") (pinfunction "2_S2") (pintype "passive"))
      (node (ref "D32") (pin "A") (pinfunction "A_A") (pintype "passive"))
    )
    (net (code "40") (name "Net-(>/.-2)") (class "Default")
      (node (ref ">/.") (pin "S2") (pinfunction "2_S2") (pintype "passive"))
      (node (ref "D77") (pin "A") (pinfunction "A_A") (pintype "passive"))
    )
    (net (code "41") (name "Net-(A-2)") (class "Default")
      (node (ref "A") (pin "S2") (pinfunction "2_S2") (pintype "passive"))
      (node (ref "D55") (pin "A") (pinfunction "A_A") (pintype "passive"))
    )
    (net (code "42") (name "Net-(B-2)") (class "Default")
      (node (ref "B") (pin "S2") (pinfunction "2_S2") (pintype "passive"))
      (node (ref "D73") (pin "A") (pinfunction "A_A") (pintype "passive"))
    )
    (net (code "43") (name "Net-(BACKSPACE-2)") (class "Default")
      (node (ref "BACKSPACE") (pin "S2") (pinfunction "2_S2") (pintype "passive"))
      (node (ref "D33") (pin "A") (pinfunction "A_A") (pintype "passive"))
    )
    (net (code "44") (name "Net-(C-2)") (class "Default")
      (node (ref "C") (pin "S2") (pinfunction "2_S2") (pintype "passive"))
      (node (ref "D71") (pin "A") (pinfunction "A_A") (pintype "passive"))
    )
    (net (code "45") (name "Net-(C1-Pad2)") (class "Default")
      (node (ref "C1") (pin "2") (pinfunction "2_2") (pintype "passive"))
      (node (ref "J4") (pin "SHLD1") (pinfunction "SHLD_SHLD1") (pintype "bidirectional"))
      (node (ref "J4") (pin "SHLD2") (pinfunction "SHLD_SHLD2") (pintype "bidirectional"))
      (node (ref "J4") (pin "SHLD3") (pinfunction "SHLD_SHLD3") (pintype "bidirectional"))
      (node (ref "J4") (pin "SHLD4") (pinfunction "SHLD_SHLD4") (pintype "bidirectional"))
      (node (ref "J4") (pin "SHLD5") (pinfunction "SHLD_SHLD5") (pintype "bidirectional"))
      (node (ref "J4") (pin "SHLD6") (pinfunction "SHLD_SHLD6") (pintype "bidirectional"))
      (node (ref "J4") (pin "SHLD7") (pinfunction "SHLD_SHLD7") (pintype "bidirectional"))
      (node (ref "J4") (pin "SHLD8") (pinfunction "SHLD_SHLD8") (pintype "bidirectional"))
      (node (ref "R8") (pin "1") (pinfunction "1_1") (pintype "passive"))
    )
    (net (code "46") (name "Net-(C4-Pad2)") (class "Default")
      (node (ref "C4") (pin "2") (pinfunction "2_2") (pintype "passive"))
      (node (ref "J1") (pin "SHLD1") (pinfunction "SHIELD_SHLD1") (pintype "bidirectional"))
      (node (ref "J1") (pin "SHLD2") (pinfunction "SHIELD_SHLD2") (pintype "bidirectional"))
      (node (ref "R10") (pin "1") (pinfunction "1_1") (pintype "passive"))
    )
    (net (code "47") (name "Net-(C6-Pad2)") (class "Default")
      (node (ref "C6") (pin "2") (pinfunction "2_2") (pintype "passive"))
      (node (ref "J2") (pin "SHLD1") (pinfunction "SHIELD_SHLD1") (pintype "bidirectional"))
      (node (ref "J2") (pin "SHLD2") (pinfunction "SHIELD_SHLD2") (pintype "bidirectional"))
      (node (ref "R13") (pin "1") (pinfunction "1_1") (pintype "passive"))
    )
    (net (code "48") (name "Net-(C8-Pad2)") (class "Default")
      (node (ref "C8") (pin "2") (pinfunction "2_2") (pintype "passive"))
      (node (ref "J3") (pin "SHLD1") (pinfunction "SHIELD_SHLD1") (pintype "bidirectional"))
      (node (ref "J3") (pin "SHLD2") (pinfunction "SHIELD_SHLD2") (pintype "bidirectional"))
      (node (ref "R16") (pin "1") (pinfunction "1_1") (pintype "passive"))
    )
    (net (code "49") (name "Net-(CAPSLOCK-2)") (class "Default")
      (node (ref "CAPSLOCK") (pin "S2") (pinfunction "2_S2") (pintype "passive"))
      (node (ref "D54") (pin "A") (pinfunction "A_A") (pintype "passive"))
    )
    (net (code "50") (name "Net-(D-2)") (class "Default")
      (node (ref "D") (pin "S2") (pinfunction "2_S2") (pintype "passive"))
      (node (ref "D57") (pin "A") (pinfunction "A_A") (pintype "passive"))
    )
    (net (code "51") (name "Net-(D-ARR-2)") (class "Default")
      (node (ref "D-ARR") (pin "S2") (pinfunction "2_S2") (pintype "passive"))
      (node (ref "D94") (pin "A") (pinfunction "A_A") (pintype "passive"))
    )
    (net (code "52") (name "Net-(D14-IO1)") (class "Default")
      (node (ref "D14") (pin "2") (pinfunction "IO1_2") (pintype "passive"))
      (node (ref "IC1") (pin "6") (pinfunction "DM3_6") (pintype "bidirectional"))
      (node (ref "R11") (pin "1") (pinfunction "1_1") (pintype "passive"))
    )
    (net (code "53") (name "Net-(D14-IO2)") (class "Default")
      (node (ref "D14") (pin "3") (pinfunction "IO2_3") (pintype "passive"))
      (node (ref "IC1") (pin "7") (pinfunction "DP3_7") (pintype "bidirectional"))
      (node (ref "R12") (pin "1") (pinfunction "1_1") (pintype "passive"))
    )
    (net (code "54") (name "Net-(D14-VCC)") (class "Default")
      (node (ref "C3") (pin "+") (pinfunction "+_+") (pintype "passive"))
      (node (ref "C5") (pin "+") (pinfunction "+_+") (pintype "passive"))
      (node (ref "C7") (pin "+") (pinfunction "+_+") (pintype "passive"))
      (node (ref "D14") (pin "4") (pinfunction "VCC_4") (pintype "passive"))
      (node (ref "D16") (pin "4") (pinfunction "VCC_4") (pintype "passive"))
      (node (ref "D18") (pin "4") (pinfunction "VCC_4") (pintype "passive"))
      (node (ref "F1") (pin "1") (pinfunction "1_1") (pintype "passive"))
      (node (ref "J1") (pin "VBUS") (pinfunction "VBUS_VBUS") (pintype "power_in"))
      (node (ref "J2") (pin "VBUS") (pinfunction "VBUS_VBUS") (pintype "power_in"))
      (node (ref "J3") (pin "VBUS") (pinfunction "VBUS_VBUS") (pintype "power_in"))
      (node (ref "R21") (pin "2") (pinfunction "2_2") (pintype "passive"))
    )
    (net (code "55") (name "Net-(D16-IO1)") (class "Default")
      (node (ref "D16") (pin "2") (pinfunction "IO1_2") (pintype "passive"))
      (node (ref "IC1") (pin "8") (pinfunction "DM2_8") (pintype "bidirectional"))
      (node (ref "R14") (pin "1") (pinfunction "1_1") (pintype "passive"))
    )
    (net (code "56") (name "Net-(D16-IO2)") (class "Default")
      (node (ref "D16") (pin "3") (pinfunction "IO2_3") (pintype "passive"))
      (node (ref "IC1") (pin "9") (pinfunction "DP2_9") (pintype "bidirectional"))
      (node (ref "R15") (pin "1") (pinfunction "1_1") (pintype "passive"))
    )
    (net (code "57") (name "Net-(D18-IO1)") (class "Default")
      (node (ref "D18") (pin "2") (pinfunction "IO1_2") (pintype "passive"))
      (node (ref "IC1") (pin "10") (pinfunction "DM1_10") (pintype "bidirectional"))
      (node (ref "R17") (pin "1") (pinfunction "1_1") (pintype "passive"))
    )
    (net (code "58") (name "Net-(D18-IO2)") (class "Default")
      (node (ref "D18") (pin "3") (pinfunction "IO2_3") (pintype "passive"))
      (node (ref "IC1") (pin "11") (pinfunction "DP1_11") (pintype "bidirectional"))
      (node (ref "R18") (pin "1") (pinfunction "1_1") (pintype "passive"))
    )
    (net (code "59") (name "Net-(DELETE-2)") (class "Default")
      (node (ref "D51") (pin "A") (pinfunction "A_A") (pintype "passive"))
      (node (ref "DELETE") (pin "S2") (pinfunction "2_S2") (pintype "passive"))
    )
    (net (code "60") (name "Net-(DOWN-2)") (class "Default")
      (node (ref "D53") (pin "A") (pinfunction "A_A") (pintype "passive"))
      (node (ref "DOWN") (pin "S2") (pinfunction "2_S2") (pintype "passive"))
    )
    (net (code "61") (name "Net-(E-2)") (class "Default")
      (node (ref "D40") (pin "A") (pinfunction "A_A") (pintype "passive"))
      (node (ref "E") (pin "S2") (pinfunction "2_S2") (pintype "passive"))
    )
    (net (code "62") (name "Net-(END-2)") (class "Default")
      (node (ref "D52") (pin "A") (pinfunction "A_A") (pintype "passive"))
      (node (ref "END") (pin "S2") (pinfunction "2_S2") (pintype "passive"))
    )
    (net (code "63") (name "Net-(ESC-2)") (class "Default")
      (node (ref "D1") (pin "A") (pinfunction "A_A") (pintype "passive"))
      (node (ref "ESC") (pin "S2") (pinfunction "2_S2") (pintype "passive"))
    )
    (net (code "64") (name "Net-(F-2)") (class "Default")
      (node (ref "D58") (pin "A") (pinfunction "A_A") (pintype "passive"))
      (node (ref "F") (pin "S2") (pinfunction "2_S2") (pintype "passive"))
    )
    (net (code "65") (name "Net-(F1-Pad2)") (class "Default")
      (node (ref "F1") (pin "2") (pinfunction "2_2") (pintype "passive"))
      (node (ref "J4") (pin "VBUS1") (pinfunction "VBUS_VBUS1") (pintype "bidirectional"))
      (node (ref "J4") (pin "VBUS2") (pinfunction "VBUS_VBUS2") (pintype "bidirectional"))
      (node (ref "R9") (pin "2") (pinfunction "2_2") (pintype "passive"))
    )
    (net (code "66") (name "Net-(F_1-2)") (class "Default")
      (node (ref "D2") (pin "A") (pinfunction "A_A") (pintype "passive"))
      (node (ref "F_1") (pin "S2") (pinfunction "2_S2") (pintype "passive"))
    )
    (net (code "67") (name "Net-(F_2-2)") (class "Default")
      (node (ref "D3") (pin "A") (pinfunction "A_A") (pintype "passive"))
      (node (ref "F_2") (pin "S2") (pinfunction "2_S2") (pintype "passive"))
    )
    (net (code "68") (name "Net-(F_3-2)") (class "Default")
      (node (ref "D4") (pin "A") (pinfunction "A_A") (pintype "passive"))
      (node (ref "F_3") (pin "S2") (pinfunction "2_S2") (pintype "passive"))
    )
    (net (code "69") (name "Net-(F_4-2)") (class "Default")
      (node (ref "D15") (pin "A") (pinfunction "A_A") (pintype "passive"))
      (node (ref "F_4") (pin "S2") (pinfunction "2_S2") (pintype "passive"))
    )
    (net (code "70") (name "Net-(F_5-2)") (class "Default")
      (node (ref "D5") (pin "A") (pinfunction "A_A") (pintype "passive"))
      (node (ref "F_5") (pin "S2") (pinfunction "2_S2") (pintype "passive"))
    )
    (net (code "71") (name "Net-(F_6-2)") (class "Default")
      (node (ref "D6") (pin "A") (pinfunction "A_A") (pintype "passive"))
      (node (ref "F_6") (pin "S2") (pinfunction "2_S2") (pintype "passive"))
    )
    (net (code "72") (name "Net-(F_7-2)") (class "Default")
      (node (ref "D7") (pin "A") (pinfunction "A_A") (pintype "passive"))
      (node (ref "F_7") (pin "S2") (pinfunction "2_S2") (pintype "passive"))
    )
    (net (code "73") (name "Net-(F_8-2)") (class "Default")
      (node (ref "D17") (pin "A") (pinfunction "A_A") (pintype "passive"))
      (node (ref "F_8") (pin "S2") (pinfunction "2_S2") (pintype "passive"))
    )
    (net (code "74") (name "Net-(F_9-2)") (class "Default")
      (node (ref "D8") (pin "A") (pinfunction "A_A") (pintype "passive"))
      (node (ref "F_9") (pin "S2") (pinfunction "2_S2") (pintype "passive"))
    )
    (net (code "75") (name "Net-(F_10-2)") (class "Default")
      (node (ref "D9") (pin "A") (pinfunction "A_A") (pintype "passive"))
      (node (ref "F_10") (pin "S2") (pinfunction "2_S2") (pintype "passive"))
    )
    (net (code "76") (name "Net-(F_11-2)") (class "Default")
      (node (ref "D10") (pin "A") (pinfunction "A_A") (pintype "passive"))
      (node (ref "F_11") (pin "S2") (pinfunction "2_S2") (pintype "passive"))
    )
    (net (code "77") (name "Net-(F_12-2)") (class "Default")
      (node (ref "D19") (pin "A") (pinfunction "A_A") (pintype "passive"))
      (node (ref "F_12") (pin "S2") (pinfunction "2_S2") (pintype "passive"))
    )
    (net (code "78") (name "Net-(G-2)") (class "Default")
      (node (ref "D59") (pin "A") (pinfunction "A_A") (pintype "passive"))
      (node (ref "G") (pin "S2") (pinfunction "2_S2") (pintype "passive"))
    )
    (net (code "79") (name "Net-(H-2)") (class "Default")
      (node (ref "D60") (pin "A") (pinfunction "A_A") (pintype "passive"))
      (node (ref "H") (pin "S2") (pinfunction "2_S2") (pintype "passive"))
    )
    (net (code "80") (name "Net-(HOME-2)") (class "Default")
      (node (ref "D35") (pin "A") (pinfunction "A_A") (pintype "passive"))
      (node (ref "HOME") (pin "S2") (pinfunction "2_S2") (pintype "passive"))
    )
    (net (code "81") (name "Net-(I-2)") (class "Default")
      (node (ref "D45") (pin "A") (pinfunction "A_A") (pintype "passive"))
      (node (ref "I") (pin "S2") (pinfunction "2_S2") (pintype "passive"))
    )
    (net (code "82") (name "Net-(IC1-BUSJ)") (class "Default")
      (node (ref "IC1") (pin "19") (pinfunction "BUSJ_19") (pintype "input"))
      (node (ref "R20") (pin "1") (pinfunction "1_1") (pintype "passive"))
    )
    (net (code "83") (name "Net-(IC1-DM4)") (class "Default")
      (node (ref "IC1") (pin "4") (pinfunction "DM4_4") (pintype "bidirectional"))
      (node (ref "IC4") (pin "3") (pinfunction "D-_3") (pintype "bidirectional"))
    )
    (net (code "84") (name "Net-(IC1-DMU)") (class "Default")
      (node (ref "IC1") (pin "15") (pinfunction "DMU_15") (pintype "bidirectional"))
      (node (ref "R4") (pin "1") (pinfunction "1_1") (pintype "passive"))
    )
    (net (code "85") (name "Net-(IC1-DP4)") (class "Default")
      (node (ref "IC1") (pin "5") (pinfunction "DP4_5") (pintype "bidirectional"))
      (node (ref "IC4") (pin "4") (pinfunction "D+_4") (pintype "bidirectional"))
    )
    (net (code "86") (name "Net-(IC1-DPU)") (class "Default")
      (node (ref "IC1") (pin "16") (pinfunction "DPU_16") (pintype "bidirectional"))
      (node (ref "R3") (pin "1") (pinfunction "1_1") (pintype "passive"))
    )
    (net (code "87") (name "Net-(IC1-OVCJ)") (class "Default")
      (node (ref "C14") (pin "2") (pinfunction "2_2") (pintype "passive"))
      (node (ref "IC1") (pin "26") (pinfunction "OVCJ_26") (pintype "input"))
      (node (ref "R21") (pin "1") (pinfunction "1_1") (pintype "passive"))
    )
    (net (code "88") (name "Net-(IC1-REXT)") (class "Default")
      (node (ref "IC1") (pin "14") (pinfunction "REXT_14") (pintype "passive"))
      (node (ref "R1") (pin "2") (pinfunction "2_2") (pintype "passive"))
    )
    (net (code "89") (name "Net-(IC1-VBUSM)") (class "Default")
      (node (ref "C2") (pin "2") (pinfunction "2_2") (pintype "passive"))
      (node (ref "IC1") (pin "18") (pinfunction "VBUSM_18") (pintype "power_in"))
      (node (ref "R19") (pin "2") (pinfunction "2_2") (pintype "passive"))
      (node (ref "R7") (pin "1") (pinfunction "1_1") (pintype "passive"))
    )
    (net (code "90") (name "Net-(IC1-XIN)") (class "Default")
      (node (ref "C9") (pin "1") (pinfunction "1_1") (pintype "passive"))
      (node (ref "IC1") (pin "3") (pinfunction "XIN_3") (pintype "passive"))
      (node (ref "X1") (pin "3") (pinfunction "2_3") (pintype "passive"))
    )
    (net (code "91") (name "Net-(IC1-XOUT)") (class "Default")
      (node (ref "C16") (pin "1") (pinfunction "1_1") (pintype "passive"))
      (node (ref "IC1") (pin "2") (pinfunction "XOUT_2") (pintype "passive"))
      (node (ref "X1") (pin "1") (pinfunction "1_1") (pintype "passive"))
    )
    (net (code "92") (name "Net-(IC1-XRSTJ)") (class "Default")
      (node (ref "IC1") (pin "17") (pinfunction "XRSTJ_17") (pintype "input"))
      (node (ref "R5") (pin "2") (pinfunction "2_2") (pintype "passive"))
    )
    (net (code "93") (name "Net-(IC3-P2)") (class "Default")
      (node (ref "IC3") (pin "12") (pinfunction "P2_12") (pintype "bidirectional"))
      (node (ref "R32") (pin "1") (pinfunction "1_1") (pintype "passive"))
    )
    (net (code "94") (name "Net-(IC3-P3)") (class "Default")
      (node (ref "IC3") (pin "14") (pinfunction "P3_14") (pintype "bidirectional"))
      (node (ref "R31") (pin "1") (pinfunction "1_1") (pintype "passive"))
    )
    (net (code "95") (name "Net-(IC3-P4)") (class "Default")
      (node (ref "IC3") (pin "16") (pinfunction "P4_16") (pintype "bidirectional"))
      (node (ref "R30") (pin "1") (pinfunction "1_1") (pintype "passive"))
    )
    (net (code "96") (name "Net-(IC3-P5)") (class "Default")
      (node (ref "IC3") (pin "17") (pinfunction "P5_17") (pintype "bidirectional"))
      (node (ref "R29") (pin "1") (pinfunction "1_1") (pintype "passive"))
    )
    (net (code "97") (name "Net-(IC3-P6)") (class "Default")
      (node (ref "IC3") (pin "19") (pinfunction "P6_19") (pintype "bidirectional"))
      (node (ref "R28") (pin "1") (pinfunction "1_1") (pintype "passive"))
    )
    (net (code "98") (name "Net-(IC3-P7)") (class "Default")
      (node (ref "IC3") (pin "20") (pinfunction "P7_20") (pintype "bidirectional"))
      (node (ref "R27") (pin "1") (pinfunction "1_1") (pintype "passive"))
    )
    (net (code "99") (name "Net-(IC4-AREF)") (class "Default")
      (node (ref "C19") (pin "2") (pinfunction "2_2") (pintype "passive"))
      (node (ref "IC4") (pin "42") (pinfunction "AREF_42") (pintype "bidirectional"))
    )
    (net (code "100") (name "Net-(IC4-PE2(~{HWB}))") (class "Default")
      (node (ref "IC4") (pin "33") (pinfunction "PE2(~{HWB})_33") (pintype "bidirectional"))
      (node (ref "R26") (pin "2") (pinfunction "2_2") (pintype "passive"))
    )
    (net (code "101") (name "Net-(IC4-UCAP)") (class "Default")
      (node (ref "C20") (pin "2") (pinfunction "2_2") (pintype "passive"))
      (node (ref "IC4") (pin "6") (pinfunction "UCAP_6") (pintype "bidirectional"))
    )
    (net (code "102") (name "Net-(IC4-XTAL1)") (class "Default")
      (node (ref "C17") (pin "1") (pinfunction "1_1") (pintype "passive"))
      (node (ref "IC4") (pin "17") (pinfunction "XTAL1_17") (pintype "bidirectional"))
      (node (ref "X2") (pin "3") (pinfunction "2_3") (pintype "passive"))
    )
    (net (code "103") (name "Net-(IC4-XTAL2)") (class "Default")
      (node (ref "C18") (pin "1") (pinfunction "1_1") (pintype "passive"))
      (node (ref "IC4") (pin "16") (pinfunction "XTAL2_16") (pintype "bidirectional"))
      (node (ref "X2") (pin "1") (pinfunction "1_1") (pintype "passive"))
    )
    (net (code "104") (name "Net-(INSERT-2)") (class "Default")
      (node (ref "D34") (pin "A") (pinfunction "A_A") (pintype "passive"))
      (node (ref "INSERT") (pin "S2") (pinfunction "2_S2") (pintype "passive"))
    )
    (net (code "105") (name "Net-(J-2)") (class "Default")
      (node (ref "D61") (pin "A") (pinfunction "A_A") (pintype "passive"))
      (node (ref "J") (pin "S2") (pinfunction "2_S2") (pintype "passive"))
    )
    (net (code "106") (name "Net-(J1-PadD+)") (class "Default")
      (node (ref "J1") (pin "D+") (pinfunction "D+_D+") (pintype "bidirectional"))
      (node (ref "R12") (pin "2") (pinfunction "2_2") (pintype "passive"))
    )
    (net (code "107") (name "Net-(J1-PadD-)") (class "Default")
      (node (ref "J1") (pin "D-") (pinfunction "D-_D-") (pintype "bidirectional"))
      (node (ref "R11") (pin "2") (pinfunction "2_2") (pintype "passive"))
    )
    (net (code "108") (name "Net-(J2-PadD+)") (class "Default")
      (node (ref "J2") (pin "D+") (pinfunction "D+_D+") (pintype "bidirectional"))
      (node (ref "R15") (pin "2") (pinfunction "2_2") (pintype "passive"))
    )
    (net (code "109") (name "Net-(J2-PadD-)") (class "Default")
      (node (ref "J2") (pin "D-") (pinfunction "D-_D-") (pintype "bidirectional"))
      (node (ref "R14") (pin "2") (pinfunction "2_2") (pintype "passive"))
    )
    (net (code "110") (name "Net-(J3-PadD+)") (class "Default")
      (node (ref "J3") (pin "D+") (pinfunction "D+_D+") (pintype "bidirectional"))
      (node (ref "R18") (pin "2") (pinfunction "2_2") (pintype "passive"))
    )
    (net (code "111") (name "Net-(J3-PadD-)") (class "Default")
      (node (ref "J3") (pin "D-") (pinfunction "D-_D-") (pintype "bidirectional"))
      (node (ref "R17") (pin "2") (pinfunction "2_2") (pintype "passive"))
    )
    (net (code "112") (name "Net-(J4-CC1)") (class "Default")
      (node (ref "J4") (pin "A5") (pinfunction "CC1_A5") (pintype "bidirectional"))
      (node (ref "R2") (pin "2") (pinfunction "2_2") (pintype "passive"))
    )
    (net (code "113") (name "Net-(J4-CC2)") (class "Default")
      (node (ref "J4") (pin "B5") (pinfunction "CC2_B5") (pintype "bidirectional"))
      (node (ref "R6") (pin "2") (pinfunction "2_2") (pintype "passive"))
    )
    (net (code "114") (name "Net-(J4-D+-PadA6)") (class "Default")
      (node (ref "J4") (pin "A6") (pinfunction "D+_A6") (pintype "bidirectional"))
      (node (ref "J4") (pin "B6") (pinfunction "D+_B6") (pintype "bidirectional"))
      (node (ref "R3") (pin "2") (pinfunction "2_2") (pintype "passive"))
    )
    (net (code "115") (name "Net-(J4-D--PadA7)") (class "Default")
      (node (ref "J4") (pin "A7") (pinfunction "D-_A7") (pintype "bidirectional"))
      (node (ref "J4") (pin "B7") (pinfunction "D-_B7") (pintype "bidirectional"))
      (node (ref "R4") (pin "2") (pinfunction "2_2") (pintype "passive"))
    )
    (net (code "116") (name "Net-(K-2)") (class "Default")
      (node (ref "D62") (pin "A") (pinfunction "A_A") (pintype "passive"))
      (node (ref "K") (pin "S2") (pinfunction "2_S2") (pintype "passive"))
    )
    (net (code "117") (name "Net-(L-2)") (class "Default")
      (node (ref "D63") (pin "A") (pinfunction "A_A") (pintype "passive"))
      (node (ref "L") (pin "S2") (pinfunction "2_S2") (pintype "passive"))
    )
    (net (code "118") (name "Net-(L-ALT-2)") (class "Default")
      (node (ref "D83") (pin "A") (pinfunction "A_A") (pintype "passive"))
      (node (ref "L-ALT") (pin "S2") (pinfunction "2_S2") (pintype "passive"))
    )
    (net (code "119") (name "Net-(L-CTRL-2)") (class "Default")
      (node (ref "D81") (pin "A") (pinfunction "A_A") (pintype "passive"))
      (node (ref "L-CTRL") (pin "S2") (pinfunction "2_S2") (pintype "passive"))
    )
    (net (code "120") (name "Net-(L-OS-2)") (class "Default")
      (node (ref "D82") (pin "A") (pinfunction "A_A") (pintype "passive"))
      (node (ref "L-OS") (pin "S2") (pinfunction "2_S2") (pintype "passive"))
    )
    (net (code "121") (name "Net-(L-SHIFT-2)") (class "Default")
      (node (ref "D67") (pin "A") (pinfunction "A_A") (pintype "passive"))
      (node (ref "L-SHIFT") (pin "S2") (pinfunction "2_S2") (pintype "passive"))
      (node (ref "L-SHIFT1") (pin "S2") (pinfunction "2_S2") (pintype "passive"))
    )
    (net (code "122") (name "Net-(LED1-C)") (class "Default")
      (node (ref "LED1") (pin "K") (pinfunction "C_K") (pintype "passive"))
      (node (ref "R27") (pin "2") (pinfunction "2_2") (pintype "passive"))
    )
    (net (code "123") (name "Net-(LED2-C)") (class "Default")
      (node (ref "LED2") (pin "K") (pinfunction "C_K") (pintype "passive"))
      (node (ref "R28") (pin "2") (pinfunction "2_2") (pintype "passive"))
    )
    (net (code "124") (name "Net-(LED3-C)") (class "Default")
      (node (ref "LED3") (pin "K") (pinfunction "C_K") (pintype "passive"))
      (node (ref "R29") (pin "2") (pinfunction "2_2") (pintype "passive"))
    )
    (net (code "125") (name "Net-(LED4-C)") (class "Default")
      (node (ref "LED4") (pin "K") (pinfunction "C_K") (pintype "passive"))
      (node (ref "R30") (pin "2") (pinfunction "2_2") (pintype "passive"))
    )
    (net (code "126") (name "Net-(LED5-C)") (class "Default")
      (node (ref "LED5") (pin "K") (pinfunction "C_K") (pintype "passive"))
      (node (ref "R31") (pin "2") (pinfunction "2_2") (pintype "passive"))
    )
    (net (code "127") (name "Net-(LED6-C)") (class "Default")
      (node (ref "LED6") (pin "K") (pinfunction "C_K") (pintype "passive"))
      (node (ref "R32") (pin "2") (pinfunction "2_2") (pintype "passive"))
    )
    (net (code "128") (name "Net-(LS1-2)") (class "Default")
      (node (ref "D84") (pin "A") (pinfunction "A_A") (pintype "passive"))
      (node (ref "LS1") (pin "S2") (pinfunction "2_S2") (pintype "passive"))
    )
    (net (code "129") (name "Net-(LS2-2)") (class "Default")
      (node (ref "D85") (pin "A") (pinfunction "A_A") (pintype "passive"))
      (node (ref "LS2") (pin "S2") (pinfunction "2_S2") (pintype "passive"))
    )
    (net (code "130") (name "Net-(L_ARR-2)") (class "Default")
      (node (ref "D93") (pin "A") (pinfunction "A_A") (pintype "passive"))
      (node (ref "L_ARR") (pin "S2") (pinfunction "2_S2") (pintype "passive"))
    )
    (net (code "131") (name "Net-(M-2)") (class "Default")
      (node (ref "D75") (pin "A") (pinfunction "A_A") (pintype "passive"))
      (node (ref "M") (pin "S2") (pinfunction "2_S2") (pintype "passive"))
    )
    (net (code "132") (name "Net-(MENU-2)") (class "Default")
      (node (ref "D91") (pin "A") (pinfunction "A_A") (pintype "passive"))
      (node (ref "MENU") (pin "S2") (pinfunction "2_S2") (pintype "passive"))
    )
    (net (code "133") (name "Net-(N-2)") (class "Default")
      (node (ref "D74") (pin "A") (pinfunction "A_A") (pintype "passive"))
      (node (ref "N") (pin "S2") (pinfunction "2_S2") (pintype "passive"))
    )
    (net (code "134") (name "Net-(O-2)") (class "Default")
      (node (ref "D46") (pin "A") (pinfunction "A_A") (pintype "passive"))
      (node (ref "O") (pin "S2") (pinfunction "2_S2") (pintype "passive"))
    )
    (net (code "135") (name "Net-(P-2)") (class "Default")
      (node (ref "D47") (pin "A") (pinfunction "A_A") (pintype "passive"))
      (node (ref "P") (pin "S2") (pinfunction "2_S2") (pintype "passive"))
    )
    (net (code "136") (name "Net-(PAUSE-2)") (class "Default")
      (node (ref "D13") (pin "A") (pinfunction "A_A") (pintype "passive"))
      (node (ref "PAUSE") (pin "S2") (pinfunction "2_S2") (pintype "passive"))
    )
    (net (code "137") (name "Net-(PRINT-2)") (class "Default")
      (node (ref "D11") (pin "A") (pinfunction "A_A") (pintype "passive"))
      (node (ref "PRINT") (pin "S2") (pinfunction "2_S2") (pintype "passive"))
    )
    (net (code "138") (name "Net-(Q-2)") (class "Default")
      (node (ref "D38") (pin "A") (pinfunction "A_A") (pintype "passive"))
      (node (ref "Q") (pin "S2") (pinfunction "2_S2") (pintype "passive"))
    )
    (net (code "139") (name "Net-(R-2)") (class "Default")
      (node (ref "D41") (pin "A") (pinfunction "A_A") (pintype "passive"))
      (node (ref "R") (pin "S2") (pinfunction "2_S2") (pintype "passive"))
    )
    (net (code "140") (name "Net-(R-ALT-2)") (class "Default")
      (node (ref "D89") (pin "A") (pinfunction "A_A") (pintype "passive"))
      (node (ref "R-ALT") (pin "S2") (pinfunction "2_S2") (pintype "passive"))
    )
    (net (code "141") (name "Net-(R-CTRL-2)") (class "Default")
      (node (ref "D92") (pin "A") (pinfunction "A_A") (pintype "passive"))
      (node (ref "R-CTRL") (pin "S2") (pinfunction "2_S2") (pintype "passive"))
    )
    (net (code "142") (name "Net-(R-OS-2)") (class "Default")
      (node (ref "D90") (pin "A") (pinfunction "A_A") (pintype "passive"))
      (node (ref "R-OS") (pin "S2") (pinfunction "2_S2") (pintype "passive"))
    )
    (net (code "143") (name "Net-(R-SHIFT-2)") (class "Default")
      (node (ref "D79") (pin "A") (pinfunction "A_A") (pintype "passive"))
      (node (ref "R-SHIFT") (pin "S2") (pinfunction "2_S2") (pintype "passive"))
    )
    (net (code "144") (name "Net-(RETURN-2)") (class "Default")
      (node (ref "D66") (pin "A") (pinfunction "A_A") (pintype "passive"))
      (node (ref "RETURN") (pin "S2") (pinfunction "2_S2") (pintype "passive"))
    )
    (net (code "145") (name "Net-(RS1-2)") (class "Default")
      (node (ref "D87") (pin "A") (pinfunction "A_A") (pintype "passive"))
      (node (ref "RS1") (pin "S2") (pinfunction "2_S2") (pintype "passive"))
    )
    (net (code "146") (name "Net-(RS2-2)") (class "Default")
      (node (ref "D88") (pin "A") (pinfunction "A_A") (pintype "passive"))
      (node (ref "RS2") (pin "S2") (pinfunction "2_S2") (pintype "passive"))
    )
    (net (code "147") (name "Net-(R_ARR-2)") (class "Default")
      (node (ref "D95") (pin "A") (pinfunction "A_A") (pintype "passive"))
      (node (ref "R_ARR") (pin "S2") (pinfunction "2_S2") (pintype "passive"))
    )
    (net (code "148") (name "Net-(S-2)") (class "Default")
      (node (ref "D56") (pin "A") (pinfunction "A_A") (pintype "passive"))
      (node (ref "S") (pin "S2") (pinfunction "2_S2") (pintype "passive"))
    )
    (net (code "149") (name "Net-(SCROLL-2)") (class "Default")
      (node (ref "D12") (pin "A") (pinfunction "A_A") (pintype "passive"))
      (node (ref "SCROLL") (pin "S2") (pinfunction "2_S2") (pintype "passive"))
    )
    (net (code "150") (name "Net-(SPACE-2)") (class "Default")
      (node (ref "D86") (pin "A") (pinfunction "A_A") (pintype "passive"))
      (node (ref "SPACE") (pin "S2") (pinfunction "2_S2") (pintype "passive"))
    )
    (net (code "151") (name "Net-(T-2)") (class "Default")
      (node (ref "D42") (pin "A") (pinfunction "A_A") (pintype "passive"))
      (node (ref "T") (pin "S2") (pinfunction "2_S2") (pintype "passive"))
    )
    (net (code "152") (name "Net-(TAB-2)") (class "Default")
      (node (ref "D37") (pin "A") (pinfunction "A_A") (pintype "passive"))
      (node (ref "TAB") (pin "S2") (pinfunction "2_S2") (pintype "passive"))
    )
    (net (code "153") (name "Net-(U-2)") (class "Default")
      (node (ref "D44") (pin "A") (pinfunction "A_A") (pintype "passive"))
      (node (ref "U") (pin "S2") (pinfunction "2_S2") (pintype "passive"))
    )
    (net (code "154") (name "Net-(UP-2)") (class "Default")
      (node (ref "D36") (pin "A") (pinfunction "A_A") (pintype "passive"))
      (node (ref "UP") (pin "S2") (pinfunction "2_S2") (pintype "passive"))
    )
    (net (code "155") (name "Net-(U_ARR-2)") (class "Default")
      (node (ref "D80") (pin "A") (pinfunction "A_A") (pintype "passive"))
      (node (ref "U_ARR") (pin "S2") (pinfunction "2_S2") (pintype "passive"))
    )
    (net (code "156") (name "Net-(V-2)") (class "Default")
      (node (ref "D72") (pin "A") (pinfunction "A_A") (pintype "passive"))
      (node (ref "V") (pin "S2") (pinfunction "2_S2") (pintype "passive"))
    )
    (net (code "157") (name "Net-(W-2)") (class "Default")
      (node (ref "D39") (pin "A") (pinfunction "A_A") (pintype "passive"))
      (node (ref "W") (pin "S2") (pinfunction "2_S2") (pintype "passive"))
    )
    (net (code "158") (name "Net-(X-2)") (class "Default")
      (node (ref "D70") (pin "A") (pinfunction "A_A") (pintype "passive"))
      (node (ref "X") (pin "S2") (pinfunction "2_S2") (pintype "passive"))
    )
    (net (code "159") (name "Net-(Y/Z-2)") (class "Default")
      (node (ref "D69") (pin "A") (pinfunction "A_A") (pintype "passive"))
      (node (ref "Y/Z") (pin "S2") (pinfunction "2_S2") (pintype "passive"))
    )
    (net (code "160") (name "Net-(Z/Y-2)") (class "Default")
      (node (ref "D43") (pin "A") (pinfunction "A_A") (pintype "passive"))
      (node (ref "Z/Y") (pin "S2") (pinfunction "2_S2") (pintype "passive"))
    )
    (net (code "161") (name "Net-([/Ü-2)") (class "Default")
      (node (ref "D48") (pin "A") (pinfunction "A_A") (pintype "passive"))
      (node (ref "[/Ü") (pin "S2") (pinfunction "2_S2") (pintype "passive"))
    )
    (net (code "162") (name "Net-(\\\\/#-2)") (class "Default")
      (node (ref "D50") (pin "A") (pinfunction "A_A") (pintype "passive"))
      (node (ref "\\\\/#") (pin "S2") (pinfunction "2_S2") (pintype "passive"))
    )
    (net (code "163") (name "Net-(]/+-2)") (class "Default")
      (node (ref "D49") (pin "A") (pinfunction "A_A") (pintype "passive"))
      (node (ref "]/+") (pin "S2") (pinfunction "2_S2") (pintype "passive"))
    )
    (net (code "164") (name "Net-(`/^-2)") (class "Default")
      (node (ref "D20") (pin "A") (pinfunction "A_A") (pintype "passive"))
      (node (ref "`/^") (pin "S2") (pinfunction "2_S2") (pintype "passive"))
    )
    (net (code "165") (name "R1") (class "Default")
      (node (ref "ESC") (pin "S1") (pinfunction "1_S1") (pintype "passive"))
      (node (ref "F_1") (pin "S1") (pinfunction "1_S1") (pintype "passive"))
      (node (ref "F_10") (pin "S1") (pinfunction "1_S1") (pintype "passive"))
      (node (ref "F_11") (pin "S1") (pinfunction "1_S1") (pintype "passive"))
      (node (ref "F_12") (pin "S1") (pinfunction "1_S1") (pintype "passive"))
      (node (ref "F_2") (pin "S1") (pinfunction "1_S1") (pintype "passive"))
      (node (ref "F_3") (pin "S1") (pinfunction "1_S1") (pintype "passive"))
      (node (ref "F_4") (pin "S1") (pinfunction "1_S1") (pintype "passive"))
      (node (ref "F_5") (pin "S1") (pinfunction "1_S1") (pintype "passive"))
      (node (ref "F_6") (pin "S1") (pinfunction "1_S1") (pintype "passive"))
      (node (ref "F_7") (pin "S1") (pinfunction "1_S1") (pintype "passive"))
      (node (ref "F_8") (pin "S1") (pinfunction "1_S1") (pintype "passive"))
      (node (ref "F_9") (pin "S1") (pinfunction "1_S1") (pintype "passive"))
      (node (ref "IC4") (pin "39") (pinfunction "PF4(ADC4/TCK)_39") (pintype "bidirectional"))
      (node (ref "PAUSE") (pin "S1") (pinfunction "1_S1") (pintype "passive"))
      (node (ref "PRINT") (pin "S1") (pinfunction "1_S1") (pintype "passive"))
      (node (ref "SCROLL") (pin "S1") (pinfunction "1_S1") (pintype "passive"))
    )
    (net (code "166") (name "R2") (class "Default")
      (node (ref "-/ß") (pin "S1") (pinfunction "1_S1") (pintype "passive"))
      (node (ref "0") (pin "S1") (pinfunction "1_S1") (pintype "passive"))
      (node (ref "1") (pin "S1") (pinfunction "1_S1") (pintype "passive"))
      (node (ref "2") (pin "S1") (pinfunction "1_S1") (pintype "passive"))
      (node (ref "3") (pin "S1") (pinfunction "1_S1") (pintype "passive"))
      (node (ref "4") (pin "S1") (pinfunction "1_S1") (pintype "passive"))
      (node (ref "5") (pin "S1") (pinfunction "1_S1") (pintype "passive"))
      (node (ref "6") (pin "S1") (pinfunction "1_S1") (pintype "passive"))
      (node (ref "7") (pin "S1") (pinfunction "1_S1") (pintype "passive"))
      (node (ref "8") (pin "S1") (pinfunction "1_S1") (pintype "passive"))
      (node (ref "9") (pin "S1") (pinfunction "1_S1") (pintype "passive"))
      (node (ref "=/´") (pin "S1") (pinfunction "1_S1") (pintype "passive"))
      (node (ref "BACKSPACE") (pin "S1") (pinfunction "1_S1") (pintype "passive"))
      (node (ref "HOME") (pin "S1") (pinfunction "1_S1") (pintype "passive"))
      (node (ref "IC4") (pin "38") (pinfunction "PF5(ADC5/TMS)_38") (pintype "bidirectional"))
      (node (ref "INSERT") (pin "S1") (pinfunction "1_S1") (pintype "passive"))
      (node (ref "UP") (pin "S1") (pinfunction "1_S1") (pintype "passive"))
      (node (ref "`/^") (pin "S1") (pinfunction "1_S1") (pintype "passive"))
    )
    (net (code "167") (name "R3") (class "Default")
      (node (ref "DELETE") (pin "S1") (pinfunction "1_S1") (pintype "passive"))
      (node (ref "DOWN") (pin "S1") (pinfunction "1_S1") (pintype "passive"))
      (node (ref "E") (pin "S1") (pinfunction "1_S1") (pintype "passive"))
      (node (ref "END") (pin "S1") (pinfunction "1_S1") (pintype "passive"))
      (node (ref "I") (pin "S1") (pinfunction "1_S1") (pintype "passive"))
      (node (ref "IC4") (pin "37") (pinfunction "PF6(ADC6/TDO)_37") (pintype "bidirectional"))
      (node (ref "O") (pin "S1") (pinfunction "1_S1") (pintype "passive"))
      (node (ref "P") (pin "S1") (pinfunction "1_S1") (pintype "passive"))
      (node (ref "Q") (pin "S1") (pinfunction "1_S1") (pintype "passive"))
      (node (ref "R") (pin "S1") (pinfunction "1_S1") (pintype "passive"))
      (node (ref "T") (pin "S1") (pinfunction "1_S1") (pintype "passive"))
      (node (ref "TAB") (pin "S1") (pinfunction "1_S1") (pintype "passive"))
      (node (ref "U") (pin "S1") (pinfunction "1_S1") (pintype "passive"))
      (node (ref "W") (pin "S1") (pinfunction "1_S1") (pintype "passive"))
      (node (ref "Z/Y") (pin "S1") (pinfunction "1_S1") (pintype "passive"))
      (node (ref "[/Ü") (pin "S1") (pinfunction "1_S1") (pintype "passive"))
      (node (ref "\\\\/#") (pin "S1") (pinfunction "1_S1") (pintype "passive"))
      (node (ref "]/+") (pin "S1") (pinfunction "1_S1") (pintype "passive"))
    )
    (net (code "168") (name "R4") (class "Default")
      (node (ref ",/Ä") (pin "S1") (pinfunction "1_S1") (pintype "passive"))
      (node (ref ".") (pin "S1") (pinfunction "1_S1") (pintype "passive"))
      (node (ref "A") (pin "S1") (pinfunction "1_S1") (pintype "passive"))
      (node (ref "CAPSLOCK") (pin "S1") (pinfunction "1_S1") (pintype "passive"))
      (node (ref "D") (pin "S1") (pinfunction "1_S1") (pintype "passive"))
      (node (ref "F") (pin "S1") (pinfunction "1_S1") (pintype "passive"))
      (node (ref "G") (pin "S1") (pinfunction "1_S1") (pintype "passive"))
      (node (ref "H") (pin "S1") (pinfunction "1_S1") (pintype "passive"))
      (node (ref "IC4") (pin "36") (pinfunction "PF7(ADC7/TDI)_36") (pintype "bidirectional"))
      (node (ref "J") (pin "S1") (pinfunction "1_S1") (pintype "passive"))
      (node (ref "K") (pin "S1") (pinfunction "1_S1") (pintype "passive"))
      (node (ref "L") (pin "S1") (pinfunction "1_S1") (pintype "passive"))
      (node (ref "RETURN") (pin "S1") (pinfunction "1_S1") (pintype "passive"))
      (node (ref "S") (pin "S1") (pinfunction "1_S1") (pintype "passive"))
    )
    (net (code "169") (name "R5") (class "Default")
      (node (ref "//-") (pin "S1") (pinfunction "1_S1") (pintype "passive"))
      (node (ref "</,") (pin "S1") (pinfunction "1_S1") (pintype "passive"))
      (node (ref "<>") (pin "S1") (pinfunction "1_S1") (pintype "passive"))
      (node (ref ">/.") (pin "S1") (pinfunction "1_S1") (pintype "passive"))
      (node (ref "B") (pin "S1") (pinfunction "1_S1") (pintype "passive"))
      (node (ref "C") (pin "S1") (pinfunction "1_S1") (pintype "passive"))
      (node (ref "IC4") (pin "41") (pinfunction "PF0(ADC0)_41") (pintype "bidirectional"))
      (node (ref "L-SHIFT") (pin "S1") (pinfunction "1_S1") (pintype "passive"))
      (node (ref "L-SHIFT1") (pin "S1") (pinfunction "1_S1") (pintype "passive"))
      (node (ref "M") (pin "S1") (pinfunction "1_S1") (pintype "passive"))
      (node (ref "N") (pin "S1") (pinfunction "1_S1") (pintype "passive"))
      (node (ref "R-SHIFT") (pin "S1") (pinfunction "1_S1") (pintype "passive"))
      (node (ref "U_ARR") (pin "S1") (pinfunction "1_S1") (pintype "passive"))
      (node (ref "V") (pin "S1") (pinfunction "1_S1") (pintype "passive"))
      (node (ref "X") (pin "S1") (pinfunction "1_S1") (pintype "passive"))
      (node (ref "Y/Z") (pin "S1") (pinfunction "1_S1") (pintype "passive"))
    )
    (net (code "170") (name "R6") (class "Default")
      (node (ref "D-ARR") (pin "S1") (pinfunction "1_S1") (pintype "passive"))
      (node (ref "IC4") (pin "40") (pinfunction "PF1(ADC1)_40") (pintype "bidirectional"))
      (node (ref "L-ALT") (pin "S1") (pinfunction "1_S1") (pintype "passive"))
      (node (ref "L-CTRL") (pin "S1") (pinfunction "1_S1") (pintype "passive"))
      (node (ref "L-OS") (pin "S1") (pinfunction "1_S1") (pintype "passive"))
      (node (ref "LS1") (pin "S1") (pinfunction "1_S1") (pintype "passive"))
      (node (ref "LS2") (pin "S1") (pinfunction "1_S1") (pintype "passive"))
      (node (ref "L_ARR") (pin "S1") (pinfunction "1_S1") (pintype "passive"))
      (node (ref "MENU") (pin "S1") (pinfunction "1_S1") (pintype "passive"))
      (node (ref "R-ALT") (pin "S1") (pinfunction "1_S1") (pintype "passive"))
      (node (ref "R-CTRL") (pin "S1") (pinfunction "1_S1") (pintype "passive"))
      (node (ref "R-OS") (pin "S1") (pinfunction "1_S1") (pintype "passive"))
      (node (ref "RS1") (pin "S1") (pinfunction "1_S1") (pintype "passive"))
      (node (ref "RS2") (pin "S1") (pinfunction "1_S1") (pintype "passive"))
      (node (ref "R_ARR") (pin "S1") (pinfunction "1_S1") (pintype "passive"))
      (node (ref "SPACE") (pin "S1") (pinfunction "1_S1") (pintype "passive"))
    )
    (net (code "171") (name "RST") (class "Default")
      (node (ref "IC4") (pin "13") (pinfunction "~{RESET}_13") (pintype "bidirectional"))
      (node (ref "ISP") (pin "RST") (pinfunction "P$3_RST") (pintype "bidirectional"))
      (node (ref "R33") (pin "2") (pinfunction "2_2") (pintype "passive"))
      (node (ref "RESET") (pin "1") (pinfunction "1_1") (pintype "passive"))
      (node (ref "RESET") (pin "2") (pinfunction "1_2") (pintype "passive"))
    )
    (net (code "172") (name "SCL") (class "Default")
      (node (ref "DISPLAY") (pin "3") (pinfunction "SCL_3") (pintype "input"))
      (node (ref "IC3") (pin "2") (pinfunction "SCL_2") (pintype "input"))
      (node (ref "IC4") (pin "18") (pinfunction "PD0(OC0B/SCL/INT0)_18") (pintype "bidirectional"))
      (node (ref "R24") (pin "2") (pinfunction "2_2") (pintype "passive"))
    )
    (net (code "173") (name "SCL_HUB") (class "Default")
      (node (ref "IC1") (pin "23") (pinfunction "LED1/EESCL_23") (pintype "bidirectional"))
      (node (ref "IC2") (pin "6") (pinfunction "SCL_6") (pintype "input"))
    )
    (net (code "174") (name "SDA") (class "Default")
      (node (ref "DISPLAY") (pin "4") (pinfunction "SDA_4") (pintype "bidirectional"))
      (node (ref "IC3") (pin "4") (pinfunction "SDA_4") (pintype "bidirectional"))
      (node (ref "IC4") (pin "19") (pinfunction "PD1(SDA/INT1)_19") (pintype "bidirectional"))
      (node (ref "R25") (pin "2") (pinfunction "2_2") (pintype "passive"))
    )
    (net (code "175") (name "SDA_HUB") (class "Default")
      (node (ref "IC1") (pin "27") (pinfunction "TESTJ/EESDA_27") (pintype "bidirectional"))
      (node (ref "IC2") (pin "5") (pinfunction "SDA_5") (pintype "bidirectional"))
    )
    (net (code "176") (name "SL_LED_A") (class "Default")
      (node (ref "R23") (pin "1") (pinfunction "1_1") (pintype "passive"))
      (node (ref "SCROLL") (pin "A") (pinfunction "A_A") (pintype "passive"))
    )
    (net (code "177") (name "SL_LED_C") (class "Default")
      (node (ref "IC3") (pin "10") (pinfunction "P0_10") (pintype "bidirectional"))
      (node (ref "SCROLL") (pin "K") (pinfunction "C_K") (pintype "passive"))
    )
    (net (code "178") (name "VCC") (class "Default")
      (node (ref "C12") (pin "2") (pinfunction "2_2") (pintype "passive"))
      (node (ref "DISPLAY") (pin "2") (pinfunction "VCC_2") (pintype "power_in"))
      (node (ref "IC1") (pin "20") (pinfunction "VDD5_20") (pintype "power_in"))
      (node (ref "IC3") (pin "5") (pinfunction "VDD_5") (pintype "power_in"))
      (node (ref "IC4") (pin "14") (pinfunction "VCC_14") (pintype "bidirectional"))
      (node (ref "IC4") (pin "2") (pinfunction "UVCC_2") (pintype "bidirectional"))
      (node (ref "IC4") (pin "24") (pinfunction "AVCC_24") (pintype "bidirectional"))
      (node (ref "IC4") (pin "34") (pinfunction "VCC_34") (pintype "bidirectional"))
      (node (ref "IC4") (pin "44") (pinfunction "AVCC_44") (pintype "bidirectional"))
      (node (ref "IC4") (pin "7") (pinfunction "VBUS_7") (pintype "bidirectional"))
      (node (ref "ISP") (pin "VCC") (pinfunction "P$6_VCC") (pintype "bidirectional"))
      (node (ref "LED1") (pin "A") (pinfunction "A_A") (pintype "passive"))
      (node (ref "LED2") (pin "A") (pinfunction "A_A") (pintype "passive"))
      (node (ref "LED3") (pin "A") (pinfunction "A_A") (pintype "passive"))
      (node (ref "LED4") (pin "A") (pinfunction "A_A") (pintype "passive"))
      (node (ref "LED5") (pin "A") (pinfunction "A_A") (pintype "passive"))
      (node (ref "LED6") (pin "A") (pinfunction "A_A") (pintype "passive"))
      (node (ref "R22") (pin "2") (pinfunction "2_2") (pintype "passive"))
      (node (ref "R23") (pin "2") (pinfunction "2_2") (pintype "passive"))
      (node (ref "R24") (pin "1") (pinfunction "1_1") (pintype "passive"))
      (node (ref "R25") (pin "1") (pinfunction "1_1") (pintype "passive"))
      (node (ref "R33") (pin "1") (pinfunction "1_1") (pintype "passive"))
      (node (ref "R7") (pin "2") (pinfunction "2_2") (pintype "passive"))
      (node (ref "R9") (pin "1") (pinfunction "1_1") (pintype "passive"))
    )
    (net (code "179") (name "unconnected-(,/Ä-C-PadK)") (class "Default")
      (node (ref ",/Ä") (pin "K") (pinfunction "C_K") (pintype "passive"))
    )
    (net (code "180") (name "unconnected-(,/Ä-PadA)") (class "Default")
      (node (ref ",/Ä") (pin "A") (pinfunction "A_A") (pintype "passive"))
    )
    (net (code "181") (name "unconnected-(-/ß-C-PadK)") (class "Default")
      (node (ref "-/ß") (pin "K") (pinfunction "C_K") (pintype "passive"))
    )
    (net (code "182") (name "unconnected-(-/ß-PadA)") (class "Default")
      (node (ref "-/ß") (pin "A") (pinfunction "A_A") (pintype "passive"))
    )
    (net (code "183") (name "unconnected-(.-C-PadK)") (class "Default")
      (node (ref ".") (pin "K") (pinfunction "C_K") (pintype "passive"))
    )
    (net (code "184") (name "unconnected-(.-PadA)") (class "Default")
      (node (ref ".") (pin "A") (pinfunction "A_A") (pintype "passive"))
    )
    (net (code "185") (name "unconnected-(//--C-PadK)") (class "Default")
      (node (ref "//-") (pin "K") (pinfunction "C_K") (pintype "passive"))
    )
    (net (code "186") (name "unconnected-(//--PadA)") (class "Default")
      (node (ref "//-") (pin "A") (pinfunction "A_A") (pintype "passive"))
    )
    (net (code "187") (name "unconnected-(0-C-PadK)") (class "Default")
      (node (ref "0") (pin "K") (pinfunction "C_K") (pintype "passive"))
    )
    (net (code "188") (name "unconnected-(0-PadA)") (class "Default")
      (node (ref "0") (pin "A") (pinfunction "A_A") (pintype "passive"))
    )
    (net (code "189") (name "unconnected-(1-C-PadK)") (class "Default")
      (node (ref "1") (pin "K") (pinfunction "C_K") (pintype "passive"))
    )
    (net (code "190") (name "unconnected-(1-PadA)") (class "Default")
      (node (ref "1") (pin "A") (pinfunction "A_A") (pintype "passive"))
    )
    (net (code "191") (name "unconnected-(2-C-PadK)") (class "Default")
      (node (ref "2") (pin "K") (pinfunction "C_K") (pintype "passive"))
    )
    (net (code "192") (name "unconnected-(2-PadA)") (class "Default")
      (node (ref "2") (pin "A") (pinfunction "A_A") (pintype "passive"))
    )
    (net (code "193") (name "unconnected-(3-C-PadK)") (class "Default")
      (node (ref "3") (pin "K") (pinfunction "C_K") (pintype "passive"))
    )
    (net (code "194") (name "unconnected-(3-PadA)") (class "Default")
      (node (ref "3") (pin "A") (pinfunction "A_A") (pintype "passive"))
    )
    (net (code "195") (name "unconnected-(4-C-PadK)") (class "Default")
      (node (ref "4") (pin "K") (pinfunction "C_K") (pintype "passive"))
    )
    (net (code "196") (name "unconnected-(4-PadA)") (class "Default")
      (node (ref "4") (pin "A") (pinfunction "A_A") (pintype "passive"))
    )
    (net (code "197") (name "unconnected-(5-C-PadK)") (class "Default")
      (node (ref "5") (pin "K") (pinfunction "C_K") (pintype "passive"))
    )
    (net (code "198") (name "unconnected-(5-PadA)") (class "Default")
      (node (ref "5") (pin "A") (pinfunction "A_A") (pintype "passive"))
    )
    (net (code "199") (name "unconnected-(6-C-PadK)") (class "Default")
      (node (ref "6") (pin "K") (pinfunction "C_K") (pintype "passive"))
    )
    (net (code "200") (name "unconnected-(6-PadA)") (class "Default")
      (node (ref "6") (pin "A") (pinfunction "A_A") (pintype "passive"))
    )
    (net (code "201") (name "unconnected-(7-C-PadK)") (class "Default")
      (node (ref "7") (pin "K") (pinfunction "C_K") (pintype "passive"))
    )
    (net (code "202") (name "unconnected-(7-PadA)") (class "Default")
      (node (ref "7") (pin "A") (pinfunction "A_A") (pintype "passive"))
    )
    (net (code "203") (name "unconnected-(8-C-PadK)") (class "Default")
      (node (ref "8") (pin "K") (pinfunction "C_K") (pintype "passive"))
    )
    (net (code "204") (name "unconnected-(8-PadA)") (class "Default")
      (node (ref "8") (pin "A") (pinfunction "A_A") (pintype "passive"))
    )
    (net (code "205") (name "unconnected-(9-C-PadK)") (class "Default")
      (node (ref "9") (pin "K") (pinfunction "C_K") (pintype "passive"))
    )
    (net (code "206") (name "unconnected-(9-PadA)") (class "Default")
      (node (ref "9") (pin "A") (pinfunction "A_A") (pintype "passive"))
    )
    (net (code "207") (name "unconnected-(</,-C-PadK)") (class "Default")
      (node (ref "</,") (pin "K") (pinfunction "C_K") (pintype "passive"))
    )
    (net (code "208") (name "unconnected-(</,-PadA)") (class "Default")
      (node (ref "</,") (pin "A") (pinfunction "A_A") (pintype "passive"))
    )
    (net (code "209") (name "unconnected-(<>-C-PadK)") (class "Default")
      (node (ref "<>") (pin "K") (pinfunction "C_K") (pintype "passive"))
    )
    (net (code "210") (name "unconnected-(<>-PadA)") (class "Default")
      (node (ref "<>") (pin "A") (pinfunction "A_A") (pintype "passive"))
    )
    (net (code "211") (name "unconnected-(=/´-C-PadK)") (class "Default")
      (node (ref "=/´") (pin "K") (pinfunction "C_K") (pintype "passive"))
    )
    (net (code "212") (name "unconnected-(=/´-PadA)") (class "Default")
      (node (ref "=/´") (pin "A") (pinfunction "A_A") (pintype "passive"))
    )
    (net (code "213") (name "unconnected-(>/.-C-PadK)") (class "Default")
      (node (ref ">/.") (pin "K") (pinfunction "C_K") (pintype "passive"))
    )
    (net (code "214") (name "unconnected-(>/.-PadA)") (class "Default")
      (node (ref ">/.") (pin "A") (pinfunction "A_A") (pintype "passive"))
    )
    (net (code "215") (name "unconnected-(A-C-PadK)") (class "Default")
      (node (ref "A") (pin "K") (pinfunction "C_K") (pintype "passive"))
    )
    (net (code "216") (name "unconnected-(A-PadA)") (class "Default")
      (node (ref "A") (pin "A") (pinfunction "A_A") (pintype "passive"))
    )
    (net (code "217") (name "unconnected-(B-C-PadK)") (class "Default")
      (node (ref "B") (pin "K") (pinfunction "C_K") (pintype "passive"))
    )
    (net (code "218") (name "unconnected-(B-PadA)") (class "Default")
      (node (ref "B") (pin "A") (pinfunction "A_A") (pintype "passive"))
    )
    (net (code "219") (name "unconnected-(BACKSPACE-C-PadK)") (class "Default")
      (node (ref "BACKSPACE") (pin "K") (pinfunction "C_K") (pintype "passive"))
    )
    (net (code "220") (name "unconnected-(BACKSPACE-PadA)") (class "Default")
      (node (ref "BACKSPACE") (pin "A") (pinfunction "A_A") (pintype "passive"))
    )
    (net (code "221") (name "unconnected-(C-C-PadK)") (class "Default")
      (node (ref "C") (pin "K") (pinfunction "C_K") (pintype "passive"))
    )
    (net (code "222") (name "unconnected-(C-PadA)") (class "Default")
      (node (ref "C") (pin "A") (pinfunction "A_A") (pintype "passive"))
    )
    (net (code "223") (name "unconnected-(D-ARR-C-PadK)") (class "Default")
      (node (ref "D-ARR") (pin "K") (pinfunction "C_K") (pintype "passive"))
    )
    (net (code "224") (name "unconnected-(D-ARR-PadA)") (class "Default")
      (node (ref "D-ARR") (pin "A") (pinfunction "A_A") (pintype "passive"))
    )
    (net (code "225") (name "unconnected-(D-C-PadK)") (class "Default")
      (node (ref "D") (pin "K") (pinfunction "C_K") (pintype "passive"))
    )
    (net (code "226") (name "unconnected-(D-PadA)") (class "Default")
      (node (ref "D") (pin "A") (pinfunction "A_A") (pintype "passive"))
    )
    (net (code "227") (name "unconnected-(DELETE-C-PadK)") (class "Default")
      (node (ref "DELETE") (pin "K") (pinfunction "C_K") (pintype "passive"))
    )
    (net (code "228") (name "unconnected-(DELETE-PadA)") (class "Default")
      (node (ref "DELETE") (pin "A") (pinfunction "A_A") (pintype "passive"))
    )
    (net (code "229") (name "unconnected-(DOWN-C-PadK)") (class "Default")
      (node (ref "DOWN") (pin "K") (pinfunction "C_K") (pintype "passive"))
    )
    (net (code "230") (name "unconnected-(DOWN-PadA)") (class "Default")
      (node (ref "DOWN") (pin "A") (pinfunction "A_A") (pintype "passive"))
    )
    (net (code "231") (name "unconnected-(E-C-PadK)") (class "Default")
      (node (ref "E") (pin "K") (pinfunction "C_K") (pintype "passive"))
    )
    (net (code "232") (name "unconnected-(E-PadA)") (class "Default")
      (node (ref "E") (pin "A") (pinfunction "A_A") (pintype "passive"))
    )
    (net (code "233") (name "unconnected-(END-C-PadK)") (class "Default")
      (node (ref "END") (pin "K") (pinfunction "C_K") (pintype "passive"))
    )
    (net (code "234") (name "unconnected-(END-PadA)") (class "Default")
      (node (ref "END") (pin "A") (pinfunction "A_A") (pintype "passive"))
    )
    (net (code "235") (name "unconnected-(ESC-C-PadK)") (class "Default")
      (node (ref "ESC") (pin "K") (pinfunction "C_K") (pintype "passive"))
    )
    (net (code "236") (name "unconnected-(ESC-PadA)") (class "Default")
      (node (ref "ESC") (pin "A") (pinfunction "A_A") (pintype "passive"))
    )
    (net (code "237") (name "unconnected-(F-C-PadK)") (class "Default")
      (node (ref "F") (pin "K") (pinfunction "C_K") (pintype "passive"))
    )
    (net (code "238") (name "unconnected-(F-PadA)") (class "Default")
      (node (ref "F") (pin "A") (pinfunction "A_A") (pintype "passive"))
    )
    (net (code "239") (name "unconnected-(F_1-C-PadK)") (class "Default")
      (node (ref "F_1") (pin "K") (pinfunction "C_K") (pintype "passive"))
    )
    (net (code "240") (name "unconnected-(F_1-PadA)") (class "Default")
      (node (ref "F_1") (pin "A") (pinfunction "A_A") (pintype "passive"))
    )
    (net (code "241") (name "unconnected-(F_2-C-PadK)") (class "Default")
      (node (ref "F_2") (pin "K") (pinfunction "C_K") (pintype "passive"))
    )
    (net (code "242") (name "unconnected-(F_2-PadA)") (class "Default")
      (node (ref "F_2") (pin "A") (pinfunction "A_A") (pintype "passive"))
    )
    (net (code "243") (name "unconnected-(F_3-C-PadK)") (class "Default")
      (node (ref "F_3") (pin "K") (pinfunction "C_K") (pintype "passive"))
    )
    (net (code "244") (name "unconnected-(F_3-PadA)") (class "Default")
      (node (ref "F_3") (pin "A") (pinfunction "A_A") (pintype "passive"))
    )
    (net (code "245") (name "unconnected-(F_4-C-PadK)") (class "Default")
      (node (ref "F_4") (pin "K") (pinfunction "C_K") (pintype "passive"))
    )
    (net (code "246") (name "unconnected-(F_4-PadA)") (class "Default")
      (node (ref "F_4") (pin "A") (pinfunction "A_A") (pintype "passive"))
    )
    (net (code "247") (name "unconnected-(F_5-C-PadK)") (class "Default")
      (node (ref "F_5") (pin "K") (pinfunction "C_K") (pintype "passive"))
    )
    (net (code "248") (name "unconnected-(F_5-PadA)") (class "Default")
      (node (ref "F_5") (pin "A") (pinfunction "A_A") (pintype "passive"))
    )
    (net (code "249") (name "unconnected-(F_6-C-PadK)") (class "Default")
      (node (ref "F_6") (pin "K") (pinfunction "C_K") (pintype "passive"))
    )
    (net (code "250") (name "unconnected-(F_6-PadA)") (class "Default")
      (node (ref "F_6") (pin "A") (pinfunction "A_A") (pintype "passive"))
    )
    (net (code "251") (name "unconnected-(F_7-C-PadK)") (class "Default")
      (node (ref "F_7") (pin "K") (pinfunction "C_K") (pintype "passive"))
    )
    (net (code "252") (name "unconnected-(F_7-PadA)") (class "Default")
      (node (ref "F_7") (pin "A") (pinfunction "A_A") (pintype "passive"))
    )
    (net (code "253") (name "unconnected-(F_8-C-PadK)") (class "Default")
      (node (ref "F_8") (pin "K") (pinfunction "C_K") (pintype "passive"))
    )
    (net (code "254") (name "unconnected-(F_8-PadA)") (class "Default")
      (node (ref "F_8") (pin "A") (pinfunction "A_A") (pintype "passive"))
    )
    (net (code "255") (name "unconnected-(F_9-C-PadK)") (class "Default")
      (node (ref "F_9") (pin "K") (pinfunction "C_K") (pintype "passive"))
    )
    (net (code "256") (name "unconnected-(F_9-PadA)") (class "Default")
      (node (ref "F_9") (pin "A") (pinfunction "A_A") (pintype "passive"))
    )
    (net (code "257") (name "unconnected-(F_10-C-PadK)") (class "Default")
      (node (ref "F_10") (pin "K") (pinfunction "C_K") (pintype "passive"))
    )
    (net (code "258") (name "unconnected-(F_10-PadA)") (class "Default")
      (node (ref "F_10") (pin "A") (pinfunction "A_A") (pintype "passive"))
    )
    (net (code "259") (name "unconnected-(F_11-C-PadK)") (class "Default")
      (node (ref "F_11") (pin "K") (pinfunction "C_K") (pintype "passive"))
    )
    (net (code "260") (name "unconnected-(F_11-PadA)") (class "Default")
      (node (ref "F_11") (pin "A") (pinfunction "A_A") (pintype "passive"))
    )
    (net (code "261") (name "unconnected-(F_12-C-PadK)") (class "Default")
      (node (ref "F_12") (pin "K") (pinfunction "C_K") (pintype "passive"))
    )
    (net (code "262") (name "unconnected-(F_12-PadA)") (class "Default")
      (node (ref "F_12") (pin "A") (pinfunction "A_A") (pintype "passive"))
    )
    (net (code "263") (name "unconnected-(G-C-PadK)") (class "Default")
      (node (ref "G") (pin "K") (pinfunction "C_K") (pintype "passive"))
    )
    (net (code "264") (name "unconnected-(G-PadA)") (class "Default")
      (node (ref "G") (pin "A") (pinfunction "A_A") (pintype "passive"))
    )
    (net (code "265") (name "unconnected-(H-C-PadK)") (class "Default")
      (node (ref "H") (pin "K") (pinfunction "C_K") (pintype "passive"))
    )
    (net (code "266") (name "unconnected-(H-PadA)") (class "Default")
      (node (ref "H") (pin "A") (pinfunction "A_A") (pintype "passive"))
    )
    (net (code "267") (name "unconnected-(H1-MOUNT-PadB3,2)") (class "Default")
      (node (ref "H1") (pin "B3,2") (pinfunction "MOUNT_B3,2") (pintype "passive"))
    )
    (net (code "268") (name "unconnected-(H2-MOUNT-PadB3,2)") (class "Default")
      (node (ref "H2") (pin "B3,2") (pinfunction "MOUNT_B3,2") (pintype "passive"))
    )
    (net (code "269") (name "unconnected-(H3-MOUNT-PadB3,2)") (class "Default")
      (node (ref "H3") (pin "B3,2") (pinfunction "MOUNT_B3,2") (pintype "passive"))
    )
    (net (code "270") (name "unconnected-(H4-MOUNT-PadB3,2)") (class "Default")
      (node (ref "H4") (pin "B3,2") (pinfunction "MOUNT_B3,2") (pintype "passive"))
    )
    (net (code "271") (name "unconnected-(H5-MOUNT-PadB3,2)") (class "Default")
      (node (ref "H5") (pin "B3,2") (pinfunction "MOUNT_B3,2") (pintype "passive"))
    )
    (net (code "272") (name "unconnected-(H6-MOUNT-PadB3,2)") (class "Default")
      (node (ref "H6") (pin "B3,2") (pinfunction "MOUNT_B3,2") (pintype "passive"))
    )
    (net (code "273") (name "unconnected-(H7-MOUNT-PadB3,2)") (class "Default")
      (node (ref "H7") (pin "B3,2") (pinfunction "MOUNT_B3,2") (pintype "passive"))
    )
    (net (code "274") (name "unconnected-(HOME-C-PadK)") (class "Default")
      (node (ref "HOME") (pin "K") (pinfunction "C_K") (pintype "passive"))
    )
    (net (code "275") (name "unconnected-(HOME-PadA)") (class "Default")
      (node (ref "HOME") (pin "A") (pinfunction "A_A") (pintype "passive"))
    )
    (net (code "276") (name "unconnected-(I-C-PadK)") (class "Default")
      (node (ref "I") (pin "K") (pinfunction "C_K") (pintype "passive"))
    )
    (net (code "277") (name "unconnected-(I-PadA)") (class "Default")
      (node (ref "I") (pin "A") (pinfunction "A_A") (pintype "passive"))
    )
    (net (code "278") (name "unconnected-(IC1-DRV-Pad22)") (class "Default")
      (node (ref "IC1") (pin "22") (pinfunction "DRV_22") (pintype "bidirectional"))
    )
    (net (code "279") (name "unconnected-(IC1-LED2-Pad24)") (class "Default")
      (node (ref "IC1") (pin "24") (pinfunction "LED2_24") (pintype "bidirectional"))
    )
    (net (code "280") (name "unconnected-(IC1-PWRJ-Pad25)") (class "Default")
      (node (ref "IC1") (pin "25") (pinfunction "PWRJ_25") (pintype "output"))
    )
    (net (code "281") (name "unconnected-(IC3-~{INT}-Pad1)") (class "Default")
      (node (ref "IC3") (pin "1") (pinfunction "~{INT}_1") (pintype "output"))
    )
    (net (code "282") (name "unconnected-(INSERT-C-PadK)") (class "Default")
      (node (ref "INSERT") (pin "K") (pinfunction "C_K") (pintype "passive"))
    )
    (net (code "283") (name "unconnected-(INSERT-PadA)") (class "Default")
      (node (ref "INSERT") (pin "A") (pinfunction "A_A") (pintype "passive"))
    )
    (net (code "284") (name "unconnected-(J-C-PadK)") (class "Default")
      (node (ref "J") (pin "K") (pinfunction "C_K") (pintype "passive"))
    )
    (net (code "285") (name "unconnected-(J-PadA)") (class "Default")
      (node (ref "J") (pin "A") (pinfunction "A_A") (pintype "passive"))
    )
    (net (code "286") (name "unconnected-(K-C-PadK)") (class "Default")
      (node (ref "K") (pin "K") (pinfunction "C_K") (pintype "passive"))
    )
    (net (code "287") (name "unconnected-(K-PadA)") (class "Default")
      (node (ref "K") (pin "A") (pinfunction "A_A") (pintype "passive"))
    )
    (net (code "288") (name "unconnected-(L-ALT-C-PadK)") (class "Default")
      (node (ref "L-ALT") (pin "K") (pinfunction "C_K") (pintype "passive"))
    )
    (net (code "289") (name "unconnected-(L-ALT-PadA)") (class "Default")
      (node (ref "L-ALT") (pin "A") (pinfunction "A_A") (pintype "passive"))
    )
    (net (code "290") (name "unconnected-(L-C-PadK)") (class "Default")
      (node (ref "L") (pin "K") (pinfunction "C_K") (pintype "passive"))
    )
    (net (code "291") (name "unconnected-(L-CTRL-C-PadK)") (class "Default")
      (node (ref "L-CTRL") (pin "K") (pinfunction "C_K") (pintype "passive"))
    )
    (net (code "292") (name "unconnected-(L-CTRL-PadA)") (class "Default")
      (node (ref "L-CTRL") (pin "A") (pinfunction "A_A") (pintype "passive"))
    )
    (net (code "293") (name "unconnected-(L-OS-C-PadK)") (class "Default")
      (node (ref "L-OS") (pin "K") (pinfunction "C_K") (pintype "passive"))
    )
    (net (code "294") (name "unconnected-(L-OS-PadA)") (class "Default")
      (node (ref "L-OS") (pin "A") (pinfunction "A_A") (pintype "passive"))
    )
    (net (code "295") (name "unconnected-(L-PadA)") (class "Default")
      (node (ref "L") (pin "A") (pinfunction "A_A") (pintype "passive"))
    )
    (net (code "296") (name "unconnected-(L-SHIFT-C-PadK)") (class "Default")
      (node (ref "L-SHIFT") (pin "K") (pinfunction "C_K") (pintype "passive"))
    )
    (net (code "297") (name "unconnected-(L-SHIFT-PadA)") (class "Default")
      (node (ref "L-SHIFT") (pin "A") (pinfunction "A_A") (pintype "passive"))
    )
    (net (code "298") (name "unconnected-(L-SHIFT1-C-PadK)") (class "Default")
      (node (ref "L-SHIFT1") (pin "K") (pinfunction "C_K") (pintype "passive"))
    )
    (net (code "299") (name "unconnected-(L-SHIFT1-PadA)") (class "Default")
      (node (ref "L-SHIFT1") (pin "A") (pinfunction "A_A") (pintype "passive"))
    )
    (net (code "300") (name "unconnected-(LS1-C-PadK)") (class "Default")
      (node (ref "LS1") (pin "K") (pinfunction "C_K") (pintype "passive"))
    )
    (net (code "301") (name "unconnected-(LS1-PadA)") (class "Default")
      (node (ref "LS1") (pin "A") (pinfunction "A_A") (pintype "passive"))
    )
    (net (code "302") (name "unconnected-(LS2-C-PadK)") (class "Default")
      (node (ref "LS2") (pin "K") (pinfunction "C_K") (pintype "passive"))
    )
    (net (code "303") (name "unconnected-(LS2-PadA)") (class "Default")
      (node (ref "LS2") (pin "A") (pinfunction "A_A") (pintype "passive"))
    )
    (net (code "304") (name "unconnected-(L_ARR-C-PadK)") (class "Default")
      (node (ref "L_ARR") (pin "K") (pinfunction "C_K") (pintype "passive"))
    )
    (net (code "305") (name "unconnected-(L_ARR-PadA)") (class "Default")
      (node (ref "L_ARR") (pin "A") (pinfunction "A_A") (pintype "passive"))
    )
    (net (code "306") (name "unconnected-(M-C-PadK)") (class "Default")
      (node (ref "M") (pin "K") (pinfunction "C_K") (pintype "passive"))
    )
    (net (code "307") (name "unconnected-(M-PadA)") (class "Default")
      (node (ref "M") (pin "A") (pinfunction "A_A") (pintype "passive"))
    )
    (net (code "308") (name "unconnected-(MENU-C-PadK)") (class "Default")
      (node (ref "MENU") (pin "K") (pinfunction "C_K") (pintype "passive"))
    )
    (net (code "309") (name "unconnected-(MENU-PadA)") (class "Default")
      (node (ref "MENU") (pin "A") (pinfunction "A_A") (pintype "passive"))
    )
    (net (code "310") (name "unconnected-(N-C-PadK)") (class "Default")
      (node (ref "N") (pin "K") (pinfunction "C_K") (pintype "passive"))
    )
    (net (code "311") (name "unconnected-(N-PadA)") (class "Default")
      (node (ref "N") (pin "A") (pinfunction "A_A") (pintype "passive"))
    )
    (net (code "312") (name "unconnected-(O-C-PadK)") (class "Default")
      (node (ref "O") (pin "K") (pinfunction "C_K") (pintype "passive"))
    )
    (net (code "313") (name "unconnected-(O-PadA)") (class "Default")
      (node (ref "O") (pin "A") (pinfunction "A_A") (pintype "passive"))
    )
    (net (code "314") (name "unconnected-(P-C-PadK)") (class "Default")
      (node (ref "P") (pin "K") (pinfunction "C_K") (pintype "passive"))
    )
    (net (code "315") (name "unconnected-(P-PadA)") (class "Default")
      (node (ref "P") (pin "A") (pinfunction "A_A") (pintype "passive"))
    )
    (net (code "316") (name "unconnected-(PAUSE-C-PadK)") (class "Default")
      (node (ref "PAUSE") (pin "K") (pinfunction "C_K") (pintype "passive"))
    )
    (net (code "317") (name "unconnected-(PAUSE-PadA)") (class "Default")
      (node (ref "PAUSE") (pin "A") (pinfunction "A_A") (pintype "passive"))
    )
    (net (code "318") (name "unconnected-(PRINT-C-PadK)") (class "Default")
      (node (ref "PRINT") (pin "K") (pinfunction "C_K") (pintype "passive"))
    )
    (net (code "319") (name "unconnected-(PRINT-PadA)") (class "Default")
      (node (ref "PRINT") (pin "A") (pinfunction "A_A") (pintype "passive"))
    )
    (net (code "320") (name "unconnected-(Q-C-PadK)") (class "Default")
      (node (ref "Q") (pin "K") (pinfunction "C_K") (pintype "passive"))
    )
    (net (code "321") (name "unconnected-(Q-PadA)") (class "Default")
      (node (ref "Q") (pin "A") (pinfunction "A_A") (pintype "passive"))
    )
    (net (code "322") (name "unconnected-(R-ALT-C-PadK)") (class "Default")
      (node (ref "R-ALT") (pin "K") (pinfunction "C_K") (pintype "passive"))
    )
    (net (code "323") (name "unconnected-(R-ALT-PadA)") (class "Default")
      (node (ref "R-ALT") (pin "A") (pinfunction "A_A") (pintype "passive"))
    )
    (net (code "324") (name "unconnected-(R-C-PadK)") (class "Default")
      (node (ref "R") (pin "K") (pinfunction "C_K") (pintype "passive"))
    )
    (net (code "325") (name "unconnected-(R-CTRL-C-PadK)") (class "Default")
      (node (ref "R-CTRL") (pin "K") (pinfunction "C_K") (pintype "passive"))
    )
    (net (code "326") (name "unconnected-(R-CTRL-PadA)") (class "Default")
      (node (ref "R-CTRL") (pin "A") (pinfunction "A_A") (pintype "passive"))
    )
    (net (code "327") (name "unconnected-(R-OS-C-PadK)") (class "Default")
      (node (ref "R-OS") (pin "K") (pinfunction "C_K") (pintype "passive"))
    )
    (net (code "328") (name "unconnected-(R-OS-PadA)") (class "Default")
      (node (ref "R-OS") (pin "A") (pinfunction "A_A") (pintype "passive"))
    )
    (net (code "329") (name "unconnected-(R-PadA)") (class "Default")
      (node (ref "R") (pin "A") (pinfunction "A_A") (pintype "passive"))
    )
    (net (code "330") (name "unconnected-(R-SHIFT-C-PadK)") (class "Default")
      (node (ref "R-SHIFT") (pin "K") (pinfunction "C_K") (pintype "passive"))
    )
    (net (code "331") (name "unconnected-(R-SHIFT-PadA)") (class "Default")
      (node (ref "R-SHIFT") (pin "A") (pinfunction "A_A") (pintype "passive"))
    )
    (net (code "332") (name "unconnected-(RETURN-C-PadK)") (class "Default")
      (node (ref "RETURN") (pin "K") (pinfunction "C_K") (pintype "passive"))
    )
    (net (code "333") (name "unconnected-(RETURN-PadA)") (class "Default")
      (node (ref "RETURN") (pin "A") (pinfunction "A_A") (pintype "passive"))
    )
    (net (code "334") (name "unconnected-(RS1-C-PadK)") (class "Default")
      (node (ref "RS1") (pin "K") (pinfunction "C_K") (pintype "passive"))
    )
    (net (code "335") (name "unconnected-(RS1-PadA)") (class "Default")
      (node (ref "RS1") (pin "A") (pinfunction "A_A") (pintype "passive"))
    )
    (net (code "336") (name "unconnected-(RS2-C-PadK)") (class "Default")
      (node (ref "RS2") (pin "K") (pinfunction "C_K") (pintype "passive"))
    )
    (net (code "337") (name "unconnected-(RS2-PadA)") (class "Default")
      (node (ref "RS2") (pin "A") (pinfunction "A_A") (pintype "passive"))
    )
    (net (code "338") (name "unconnected-(R_ARR-C-PadK)") (class "Default")
      (node (ref "R_ARR") (pin "K") (pinfunction "C_K") (pintype "passive"))
    )
    (net (code "339") (name "unconnected-(R_ARR-PadA)") (class "Default")
      (node (ref "R_ARR") (pin "A") (pinfunction "A_A") (pintype "passive"))
    )
    (net (code "340") (name "unconnected-(S-C-PadK)") (class "Default")
      (node (ref "S") (pin "K") (pinfunction "C_K") (pintype "passive"))
    )
    (net (code "341") (name "unconnected-(S-PadA)") (class "Default")
      (node (ref "S") (pin "A") (pinfunction "A_A") (pintype "passive"))
    )
    (net (code "342") (name "unconnected-(SPACE-C-PadK)") (class "Default")
      (node (ref "SPACE") (pin "K") (pinfunction "C_K") (pintype "passive"))
    )
    (net (code "343") (name "unconnected-(SPACE-PadA)") (class "Default")
      (node (ref "SPACE") (pin "A") (pinfunction "A_A") (pintype "passive"))
    )
    (net (code "344") (name "unconnected-(T-C-PadK)") (class "Default")
      (node (ref "T") (pin "K") (pinfunction "C_K") (pintype "passive"))
    )
    (net (code "345") (name "unconnected-(T-PadA)") (class "Default")
      (node (ref "T") (pin "A") (pinfunction "A_A") (pintype "passive"))
    )
    (net (code "346") (name "unconnected-(TAB-C-PadK)") (class "Default")
      (node (ref "TAB") (pin "K") (pinfunction "C_K") (pintype "passive"))
    )
    (net (code "347") (name "unconnected-(TAB-PadA)") (class "Default")
      (node (ref "TAB") (pin "A") (pinfunction "A_A") (pintype "passive"))
    )
    (net (code "348") (name "unconnected-(U-C-PadK)") (class "Default")
      (node (ref "U") (pin "K") (pinfunction "C_K") (pintype "passive"))
    )
    (net (code "349") (name "unconnected-(U-PadA)") (class "Default")
      (node (ref "U") (pin "A") (pinfunction "A_A") (pintype "passive"))
    )
    (net (code "350") (name "unconnected-(UP-C-PadK)") (class "Default")
      (node (ref "UP") (pin "K") (pinfunction "C_K") (pintype "passive"))
    )
    (net (code "351") (name "unconnected-(UP-PadA)") (class "Default")
      (node (ref "UP") (pin "A") (pinfunction "A_A") (pintype "passive"))
    )
    (net (code "352") (name "unconnected-(U_ARR-C-PadK)") (class "Default")
      (node (ref "U_ARR") (pin "K") (pinfunction "C_K") (pintype "passive"))
    )
    (net (code "353") (name "unconnected-(U_ARR-PadA)") (class "Default")
      (node (ref "U_ARR") (pin "A") (pinfunction "A_A") (pintype "passive"))
    )
    (net (code "354") (name "unconnected-(V-C-PadK)") (class "Default")
      (node (ref "V") (pin "K") (pinfunction "C_K") (pintype "passive"))
    )
    (net (code "355") (name "unconnected-(V-PadA)") (class "Default")
      (node (ref "V") (pin "A") (pinfunction "A_A") (pintype "passive"))
    )
    (net (code "356") (name "unconnected-(W-C-PadK)") (class "Default")
      (node (ref "W") (pin "K") (pinfunction "C_K") (pintype "passive"))
    )
    (net (code "357") (name "unconnected-(W-PadA)") (class "Default")
      (node (ref "W") (pin "A") (pinfunction "A_A") (pintype "passive"))
    )
    (net (code "358") (name "unconnected-(X-C-PadK)") (class "Default")
      (node (ref "X") (pin "K") (pinfunction "C_K") (pintype "passive"))
    )
    (net (code "359") (name "unconnected-(X-PadA)") (class "Default")
      (node (ref "X") (pin "A") (pinfunction "A_A") (pintype "passive"))
    )
    (net (code "360") (name "unconnected-(Y/Z-C-PadK)") (class "Default")
      (node (ref "Y/Z") (pin "K") (pinfunction "C_K") (pintype "passive"))
    )
    (net (code "361") (name "unconnected-(Y/Z-PadA)") (class "Default")
      (node (ref "Y/Z") (pin "A") (pinfunction "A_A") (pintype "passive"))
    )
    (net (code "362") (name "unconnected-(Z/Y-C-PadK)") (class "Default")
      (node (ref "Z/Y") (pin "K") (pinfunction "C_K") (pintype "passive"))
    )
    (net (code "363") (name "unconnected-(Z/Y-PadA)") (class "Default")
      (node (ref "Z/Y") (pin "A") (pinfunction "A_A") (pintype "passive"))
    )
    (net (code "364") (name "unconnected-([/Ü-C-PadK)") (class "Default")
      (node (ref "[/Ü") (pin "K") (pinfunction "C_K") (pintype "passive"))
    )
    (net (code "365") (name "unconnected-([/Ü-PadA)") (class "Default")
      (node (ref "[/Ü") (pin "A") (pinfunction "A_A") (pintype "passive"))
    )
    (net (code "366") (name "unconnected-(\\\\/#-C-PadK)") (class "Default")
      (node (ref "\\\\/#") (pin "K") (pinfunction "C_K") (pintype "passive"))
    )
    (net (code "367") (name "unconnected-(\\\\/#-PadA)") (class "Default")
      (node (ref "\\\\/#") (pin "A") (pinfunction "A_A") (pintype "passive"))
    )
    (net (code "368") (name "unconnected-(]/+-C-PadK)") (class "Default")
      (node (ref "]/+") (pin "K") (pinfunction "C_K") (pintype "passive"))
    )
    (net (code "369") (name "unconnected-(]/+-PadA)") (class "Default")
      (node (ref "]/+") (pin "A") (pinfunction "A_A") (pintype "passive"))
    )
    (net (code "370") (name "unconnected-(`/^-C-PadK)") (class "Default")
      (node (ref "`/^") (pin "K") (pinfunction "C_K") (pintype "passive"))
    )
    (net (code "371") (name "unconnected-(`/^-PadA)") (class "Default")
      (node (ref "`/^") (pin "A") (pinfunction "A_A") (pintype "passive"))
    )
  )
)
